# CPU_Power.net
KiCad netlist of a schematic drawn in Altium Designer
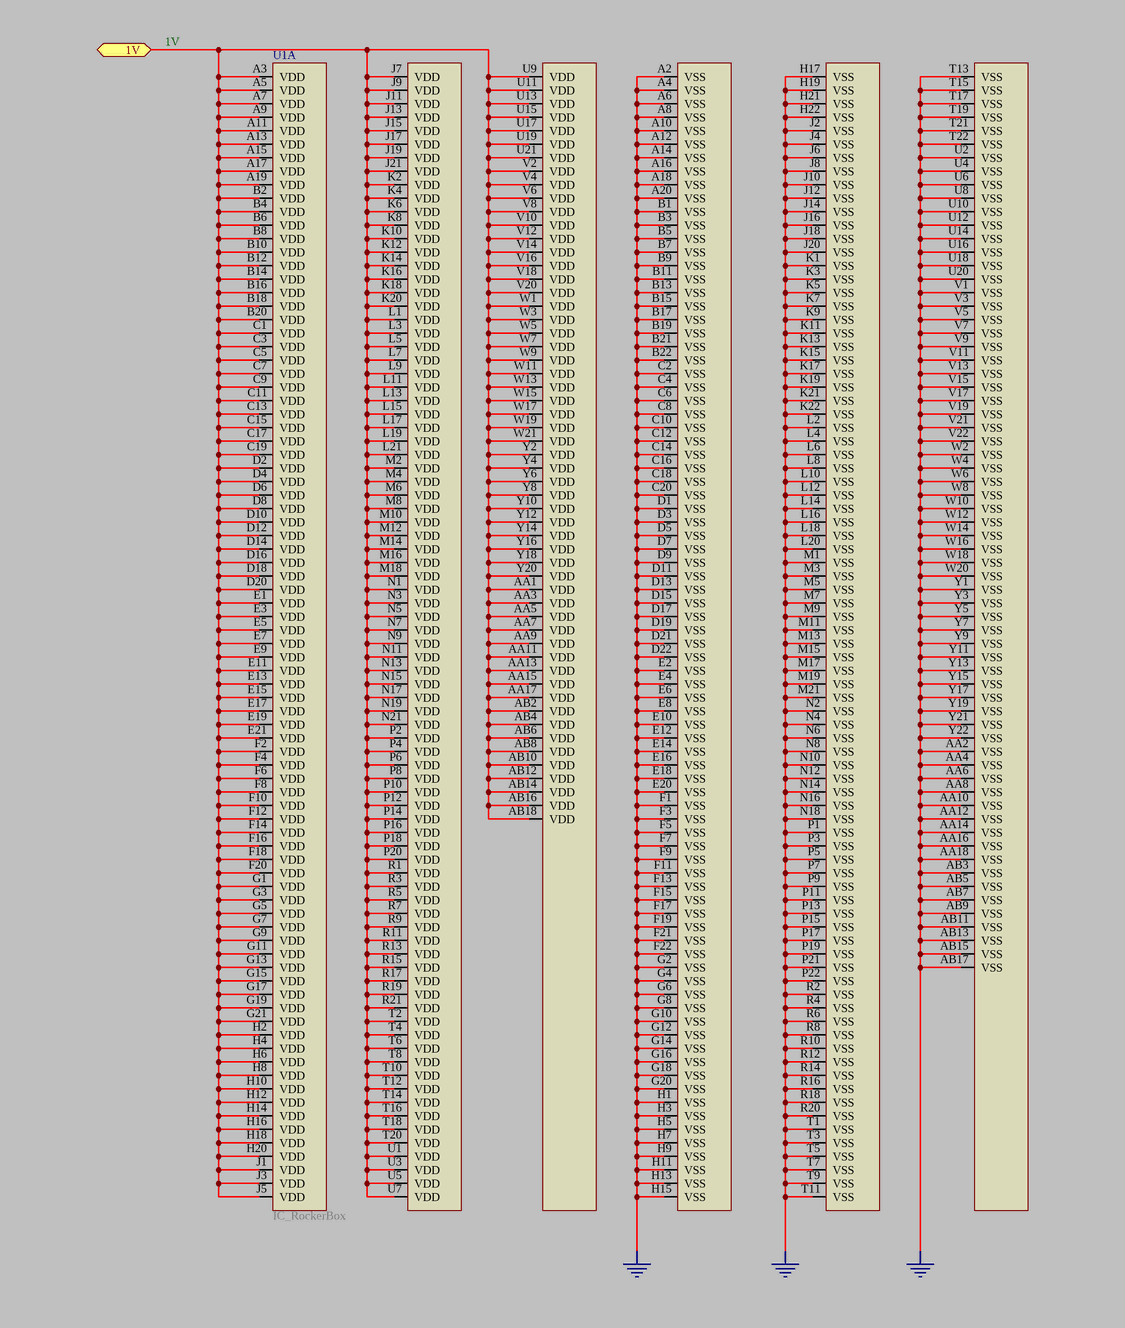
[diagram p0: CPU_Power.SchDoc, top left]
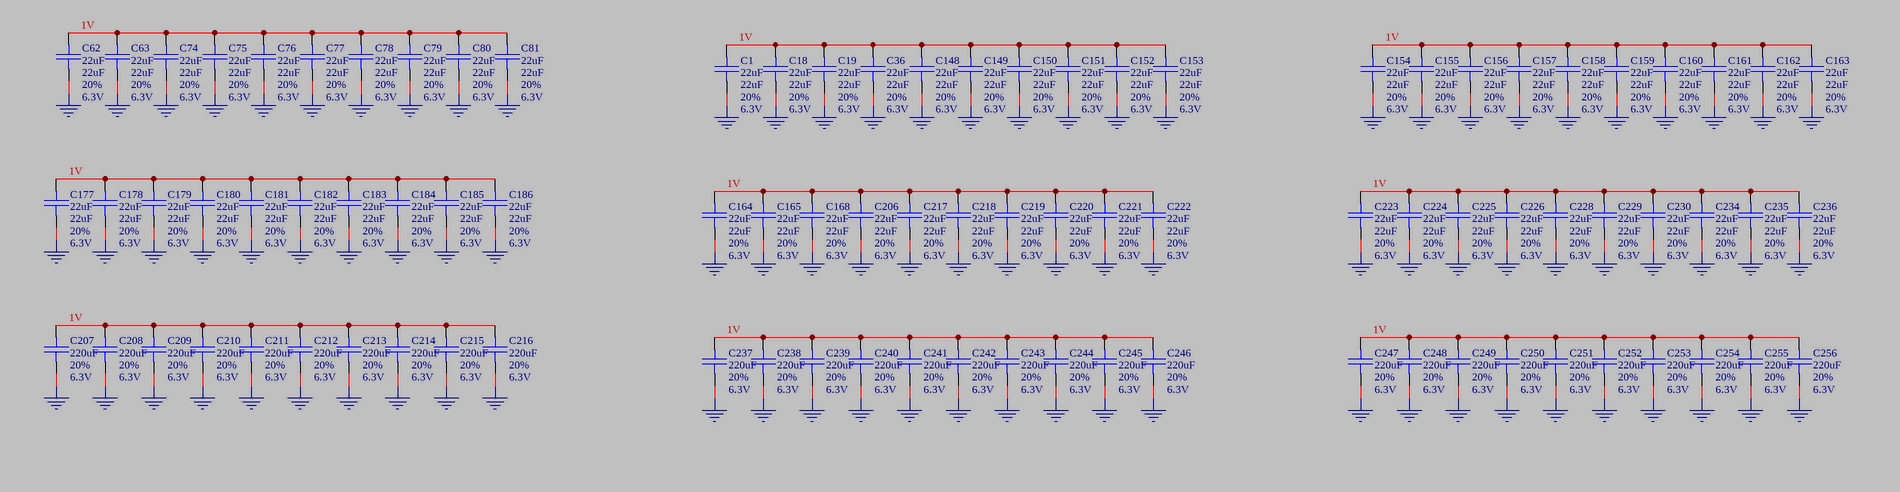
[diagram p1: CPU_Power.SchDoc, bottom left]
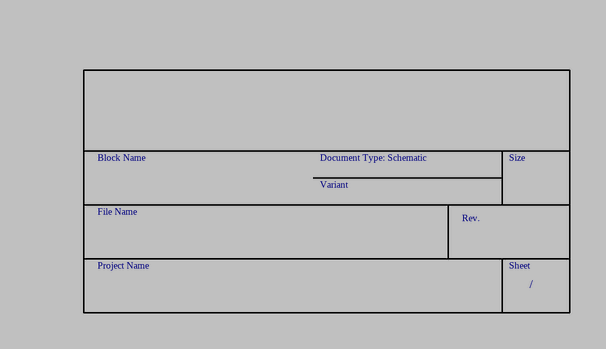
[diagram p2: CPU_Power.SchDoc, bottom right]

(export (version "E")
  (design (tool "Eeschema 10.0.6"))
  (components
    (comp (ref "C1")
      (value "22uF")
      (footprint "SMD_0805_CAPC2012X145N")
      (fields
        (field (name "DB_PART_NUMBER") "CAP000043686")
        (field (name "DB_VALUE") "22uF")
        (field (name "DB_TOLERANCE") "20%")
        (field (name "DB_VOLTAGE") "6.3V")
        (field (name "DB_MANUFACTURER_PART") "KEMET    C0805C226M9PAC")
        (field (name "DB_APPROVED_BY") "ISHIDDEN=T")
      )
      (libsource (lib "Database_Libs1") (part "C"))
    )
    (comp (ref "C18")
      (value "22uF")
      (footprint "SMD_0805_CAPC2012X145N")
      (fields
        (field (name "DB_PART_NUMBER") "CAP000043686")
        (field (name "DB_VALUE") "22uF")
        (field (name "DB_TOLERANCE") "20%")
        (field (name "DB_VOLTAGE") "6.3V")
        (field (name "DB_MANUFACTURER_PART") "KEMET    C0805C226M9PAC")
        (field (name "DB_APPROVED_BY") "ISHIDDEN=T")
      )
      (libsource (lib "Database_Libs1") (part "C"))
    )
    (comp (ref "C19")
      (value "22uF")
      (footprint "SMD_0805_CAPC2012X145N")
      (fields
        (field (name "DB_PART_NUMBER") "CAP000043686")
        (field (name "DB_VALUE") "22uF")
        (field (name "DB_TOLERANCE") "20%")
        (field (name "DB_VOLTAGE") "6.3V")
        (field (name "DB_MANUFACTURER_PART") "KEMET    C0805C226M9PAC")
        (field (name "DB_APPROVED_BY") "ISHIDDEN=T")
      )
      (libsource (lib "Database_Libs1") (part "C"))
    )
    (comp (ref "C36")
      (value "22uF")
      (footprint "SMD_0805_CAPC2012X145N")
      (fields
        (field (name "DB_PART_NUMBER") "CAP000043686")
        (field (name "DB_VALUE") "22uF")
        (field (name "DB_TOLERANCE") "20%")
        (field (name "DB_VOLTAGE") "6.3V")
        (field (name "DB_MANUFACTURER_PART") "KEMET    C0805C226M9PAC")
        (field (name "DB_APPROVED_BY") "ISHIDDEN=T")
      )
      (libsource (lib "Database_Libs1") (part "C"))
    )
    (comp (ref "C62")
      (value "22uF")
      (footprint "SMD_0805_CAPC2012X145N")
      (fields
        (field (name "DB_PART_NUMBER") "CAP000043686")
        (field (name "DB_VALUE") "22uF")
        (field (name "DB_TOLERANCE") "20%")
        (field (name "DB_VOLTAGE") "6.3V")
        (field (name "DB_MANUFACTURER_PART") "KEMET    C0805C226M9PAC")
        (field (name "DB_APPROVED_BY") "ISHIDDEN=T")
      )
      (libsource (lib "Database_Libs1") (part "C"))
    )
    (comp (ref "C63")
      (value "22uF")
      (footprint "SMD_0805_CAPC2012X145N")
      (fields
        (field (name "DB_PART_NUMBER") "CAP000043686")
        (field (name "DB_VALUE") "22uF")
        (field (name "DB_TOLERANCE") "20%")
        (field (name "DB_VOLTAGE") "6.3V")
        (field (name "DB_MANUFACTURER_PART") "KEMET    C0805C226M9PAC")
        (field (name "DB_APPROVED_BY") "ISHIDDEN=T")
      )
      (libsource (lib "Database_Libs1") (part "C"))
    )
    (comp (ref "C74")
      (value "22uF")
      (footprint "SMD_0805_CAPC2012X145N")
      (fields
        (field (name "DB_PART_NUMBER") "CAP000043686")
        (field (name "DB_VALUE") "22uF")
        (field (name "DB_TOLERANCE") "20%")
        (field (name "DB_VOLTAGE") "6.3V")
        (field (name "DB_MANUFACTURER_PART") "KEMET    C0805C226M9PAC")
        (field (name "DB_APPROVED_BY") "ISHIDDEN=T")
      )
      (libsource (lib "Database_Libs1") (part "C"))
    )
    (comp (ref "C75")
      (value "22uF")
      (footprint "SMD_0805_CAPC2012X145N")
      (fields
        (field (name "DB_PART_NUMBER") "CAP000043686")
        (field (name "DB_VALUE") "22uF")
        (field (name "DB_TOLERANCE") "20%")
        (field (name "DB_VOLTAGE") "6.3V")
        (field (name "DB_MANUFACTURER_PART") "KEMET    C0805C226M9PAC")
        (field (name "DB_APPROVED_BY") "ISHIDDEN=T")
      )
      (libsource (lib "Database_Libs1") (part "C"))
    )
    (comp (ref "C76")
      (value "22uF")
      (footprint "SMD_0805_CAPC2012X145N")
      (fields
        (field (name "DB_PART_NUMBER") "CAP000043686")
        (field (name "DB_VALUE") "22uF")
        (field (name "DB_TOLERANCE") "20%")
        (field (name "DB_VOLTAGE") "6.3V")
        (field (name "DB_MANUFACTURER_PART") "KEMET    C0805C226M9PAC")
        (field (name "DB_APPROVED_BY") "ISHIDDEN=T")
      )
      (libsource (lib "Database_Libs1") (part "C"))
    )
    (comp (ref "C77")
      (value "22uF")
      (footprint "SMD_0805_CAPC2012X145N")
      (fields
        (field (name "DB_PART_NUMBER") "CAP000043686")
        (field (name "DB_VALUE") "22uF")
        (field (name "DB_TOLERANCE") "20%")
        (field (name "DB_VOLTAGE") "6.3V")
        (field (name "DB_MANUFACTURER_PART") "KEMET    C0805C226M9PAC")
        (field (name "DB_APPROVED_BY") "ISHIDDEN=T")
      )
      (libsource (lib "Database_Libs1") (part "C"))
    )
    (comp (ref "C78")
      (value "22uF")
      (footprint "SMD_0805_CAPC2012X145N")
      (fields
        (field (name "DB_PART_NUMBER") "CAP000043686")
        (field (name "DB_VALUE") "22uF")
        (field (name "DB_TOLERANCE") "20%")
        (field (name "DB_VOLTAGE") "6.3V")
        (field (name "DB_MANUFACTURER_PART") "KEMET    C0805C226M9PAC")
        (field (name "DB_APPROVED_BY") "ISHIDDEN=T")
      )
      (libsource (lib "Database_Libs1") (part "C"))
    )
    (comp (ref "C79")
      (value "22uF")
      (footprint "SMD_0805_CAPC2012X145N")
      (fields
        (field (name "DB_PART_NUMBER") "CAP000043686")
        (field (name "DB_VALUE") "22uF")
        (field (name "DB_TOLERANCE") "20%")
        (field (name "DB_VOLTAGE") "6.3V")
        (field (name "DB_MANUFACTURER_PART") "KEMET    C0805C226M9PAC")
        (field (name "DB_APPROVED_BY") "ISHIDDEN=T")
      )
      (libsource (lib "Database_Libs1") (part "C"))
    )
    (comp (ref "C80")
      (value "22uF")
      (footprint "SMD_0805_CAPC2012X145N")
      (fields
        (field (name "DB_PART_NUMBER") "CAP000043686")
        (field (name "DB_VALUE") "22uF")
        (field (name "DB_TOLERANCE") "20%")
        (field (name "DB_VOLTAGE") "6.3V")
        (field (name "DB_MANUFACTURER_PART") "KEMET    C0805C226M9PAC")
        (field (name "DB_APPROVED_BY") "ISHIDDEN=T")
      )
      (libsource (lib "Database_Libs1") (part "C"))
    )
    (comp (ref "C81")
      (value "22uF")
      (footprint "SMD_0805_CAPC2012X145N")
      (fields
        (field (name "DB_PART_NUMBER") "CAP000043686")
        (field (name "DB_VALUE") "22uF")
        (field (name "DB_TOLERANCE") "20%")
        (field (name "DB_VOLTAGE") "6.3V")
        (field (name "DB_MANUFACTURER_PART") "KEMET    C0805C226M9PAC")
        (field (name "DB_APPROVED_BY") "ISHIDDEN=T")
      )
      (libsource (lib "Database_Libs1") (part "C"))
    )
    (comp (ref "C148")
      (value "22uF")
      (footprint "SMD_0805_CAPC2012X145N")
      (fields
        (field (name "DB_PART_NUMBER") "CAP000043686")
        (field (name "DB_VALUE") "22uF")
        (field (name "DB_TOLERANCE") "20%")
        (field (name "DB_VOLTAGE") "6.3V")
        (field (name "DB_MANUFACTURER_PART") "KEMET    C0805C226M9PAC")
        (field (name "DB_APPROVED_BY") "ISHIDDEN=T")
      )
      (libsource (lib "Database_Libs1") (part "C"))
    )
    (comp (ref "C149")
      (value "22uF")
      (footprint "SMD_0805_CAPC2012X145N")
      (fields
        (field (name "DB_PART_NUMBER") "CAP000043686")
        (field (name "DB_VALUE") "22uF")
        (field (name "DB_TOLERANCE") "20%")
        (field (name "DB_VOLTAGE") "6.3V")
        (field (name "DB_MANUFACTURER_PART") "KEMET    C0805C226M9PAC")
        (field (name "DB_APPROVED_BY") "ISHIDDEN=T")
      )
      (libsource (lib "Database_Libs1") (part "C"))
    )
    (comp (ref "C150")
      (value "22uF")
      (footprint "SMD_0805_CAPC2012X145N")
      (fields
        (field (name "DB_PART_NUMBER") "CAP000043686")
        (field (name "DB_VALUE") "22uF")
        (field (name "DB_TOLERANCE") "20%")
        (field (name "DB_VOLTAGE") "6.3V")
        (field (name "DB_MANUFACTURER_PART") "KEMET    C0805C226M9PAC")
        (field (name "DB_APPROVED_BY") "ISHIDDEN=T")
      )
      (libsource (lib "Database_Libs1") (part "C"))
    )
    (comp (ref "C151")
      (value "22uF")
      (footprint "SMD_0805_CAPC2012X145N")
      (fields
        (field (name "DB_PART_NUMBER") "CAP000043686")
        (field (name "DB_VALUE") "22uF")
        (field (name "DB_TOLERANCE") "20%")
        (field (name "DB_VOLTAGE") "6.3V")
        (field (name "DB_MANUFACTURER_PART") "KEMET    C0805C226M9PAC")
        (field (name "DB_APPROVED_BY") "ISHIDDEN=T")
      )
      (libsource (lib "Database_Libs1") (part "C"))
    )
    (comp (ref "C152")
      (value "22uF")
      (footprint "SMD_0805_CAPC2012X145N")
      (fields
        (field (name "DB_PART_NUMBER") "CAP000043686")
        (field (name "DB_VALUE") "22uF")
        (field (name "DB_TOLERANCE") "20%")
        (field (name "DB_VOLTAGE") "6.3V")
        (field (name "DB_MANUFACTURER_PART") "KEMET    C0805C226M9PAC")
        (field (name "DB_APPROVED_BY") "ISHIDDEN=T")
      )
      (libsource (lib "Database_Libs1") (part "C"))
    )
    (comp (ref "C153")
      (value "22uF")
      (footprint "SMD_0805_CAPC2012X145N")
      (fields
        (field (name "DB_PART_NUMBER") "CAP000043686")
        (field (name "DB_VALUE") "22uF")
        (field (name "DB_TOLERANCE") "20%")
        (field (name "DB_VOLTAGE") "6.3V")
        (field (name "DB_MANUFACTURER_PART") "KEMET    C0805C226M9PAC")
        (field (name "DB_APPROVED_BY") "ISHIDDEN=T")
      )
      (libsource (lib "Database_Libs1") (part "C"))
    )
    (comp (ref "C154")
      (value "22uF")
      (footprint "SMD_0805_CAPC2012X145N")
      (fields
        (field (name "DB_PART_NUMBER") "CAP000043686")
        (field (name "DB_VALUE") "22uF")
        (field (name "DB_TOLERANCE") "20%")
        (field (name "DB_VOLTAGE") "6.3V")
        (field (name "DB_MANUFACTURER_PART") "KEMET    C0805C226M9PAC")
        (field (name "DB_APPROVED_BY") "ISHIDDEN=T")
      )
      (libsource (lib "Database_Libs1") (part "C"))
    )
    (comp (ref "C155")
      (value "22uF")
      (footprint "SMD_0805_CAPC2012X145N")
      (fields
        (field (name "DB_PART_NUMBER") "CAP000043686")
        (field (name "DB_VALUE") "22uF")
        (field (name "DB_TOLERANCE") "20%")
        (field (name "DB_VOLTAGE") "6.3V")
        (field (name "DB_MANUFACTURER_PART") "KEMET    C0805C226M9PAC")
        (field (name "DB_APPROVED_BY") "ISHIDDEN=T")
      )
      (libsource (lib "Database_Libs1") (part "C"))
    )
    (comp (ref "C156")
      (value "22uF")
      (footprint "SMD_0805_CAPC2012X145N")
      (fields
        (field (name "DB_PART_NUMBER") "CAP000043686")
        (field (name "DB_VALUE") "22uF")
        (field (name "DB_TOLERANCE") "20%")
        (field (name "DB_VOLTAGE") "6.3V")
        (field (name "DB_MANUFACTURER_PART") "KEMET    C0805C226M9PAC")
        (field (name "DB_APPROVED_BY") "ISHIDDEN=T")
      )
      (libsource (lib "Database_Libs1") (part "C"))
    )
    (comp (ref "C157")
      (value "22uF")
      (footprint "SMD_0805_CAPC2012X145N")
      (fields
        (field (name "DB_PART_NUMBER") "CAP000043686")
        (field (name "DB_VALUE") "22uF")
        (field (name "DB_TOLERANCE") "20%")
        (field (name "DB_VOLTAGE") "6.3V")
        (field (name "DB_MANUFACTURER_PART") "KEMET    C0805C226M9PAC")
        (field (name "DB_APPROVED_BY") "ISHIDDEN=T")
      )
      (libsource (lib "Database_Libs1") (part "C"))
    )
    (comp (ref "C158")
      (value "22uF")
      (footprint "SMD_0805_CAPC2012X145N")
      (fields
        (field (name "DB_PART_NUMBER") "CAP000043686")
        (field (name "DB_VALUE") "22uF")
        (field (name "DB_TOLERANCE") "20%")
        (field (name "DB_VOLTAGE") "6.3V")
        (field (name "DB_MANUFACTURER_PART") "KEMET    C0805C226M9PAC")
        (field (name "DB_APPROVED_BY") "ISHIDDEN=T")
      )
      (libsource (lib "Database_Libs1") (part "C"))
    )
    (comp (ref "C159")
      (value "22uF")
      (footprint "SMD_0805_CAPC2012X145N")
      (fields
        (field (name "DB_PART_NUMBER") "CAP000043686")
        (field (name "DB_VALUE") "22uF")
        (field (name "DB_TOLERANCE") "20%")
        (field (name "DB_VOLTAGE") "6.3V")
        (field (name "DB_MANUFACTURER_PART") "KEMET    C0805C226M9PAC")
        (field (name "DB_APPROVED_BY") "ISHIDDEN=T")
      )
      (libsource (lib "Database_Libs1") (part "C"))
    )
    (comp (ref "C160")
      (value "22uF")
      (footprint "SMD_0805_CAPC2012X145N")
      (fields
        (field (name "DB_PART_NUMBER") "CAP000043686")
        (field (name "DB_VALUE") "22uF")
        (field (name "DB_TOLERANCE") "20%")
        (field (name "DB_VOLTAGE") "6.3V")
        (field (name "DB_MANUFACTURER_PART") "KEMET    C0805C226M9PAC")
        (field (name "DB_APPROVED_BY") "ISHIDDEN=T")
      )
      (libsource (lib "Database_Libs1") (part "C"))
    )
    (comp (ref "C161")
      (value "22uF")
      (footprint "SMD_0805_CAPC2012X145N")
      (fields
        (field (name "DB_PART_NUMBER") "CAP000043686")
        (field (name "DB_VALUE") "22uF")
        (field (name "DB_TOLERANCE") "20%")
        (field (name "DB_VOLTAGE") "6.3V")
        (field (name "DB_MANUFACTURER_PART") "KEMET    C0805C226M9PAC")
        (field (name "DB_APPROVED_BY") "ISHIDDEN=T")
      )
      (libsource (lib "Database_Libs1") (part "C"))
    )
    (comp (ref "C162")
      (value "22uF")
      (footprint "SMD_0805_CAPC2012X145N")
      (fields
        (field (name "DB_PART_NUMBER") "CAP000043686")
        (field (name "DB_VALUE") "22uF")
        (field (name "DB_TOLERANCE") "20%")
        (field (name "DB_VOLTAGE") "6.3V")
        (field (name "DB_MANUFACTURER_PART") "KEMET    C0805C226M9PAC")
        (field (name "DB_APPROVED_BY") "ISHIDDEN=T")
      )
      (libsource (lib "Database_Libs1") (part "C"))
    )
    (comp (ref "C163")
      (value "22uF")
      (footprint "SMD_0805_CAPC2012X145N")
      (fields
        (field (name "DB_PART_NUMBER") "CAP000043686")
        (field (name "DB_VALUE") "22uF")
        (field (name "DB_TOLERANCE") "20%")
        (field (name "DB_VOLTAGE") "6.3V")
        (field (name "DB_MANUFACTURER_PART") "KEMET    C0805C226M9PAC")
        (field (name "DB_APPROVED_BY") "ISHIDDEN=T")
      )
      (libsource (lib "Database_Libs1") (part "C"))
    )
    (comp (ref "C164")
      (value "22uF")
      (footprint "SMD_0805_CAPC2012X145N")
      (fields
        (field (name "DB_PART_NUMBER") "CAP000043686")
        (field (name "DB_VALUE") "22uF")
        (field (name "DB_TOLERANCE") "20%")
        (field (name "DB_VOLTAGE") "6.3V")
        (field (name "DB_MANUFACTURER_PART") "KEMET    C0805C226M9PAC")
        (field (name "DB_APPROVED_BY") "ISHIDDEN=T")
      )
      (libsource (lib "Database_Libs1") (part "C"))
    )
    (comp (ref "C165")
      (value "22uF")
      (footprint "SMD_0805_CAPC2012X145N")
      (fields
        (field (name "DB_PART_NUMBER") "CAP000043686")
        (field (name "DB_VALUE") "22uF")
        (field (name "DB_TOLERANCE") "20%")
        (field (name "DB_VOLTAGE") "6.3V")
        (field (name "DB_MANUFACTURER_PART") "KEMET    C0805C226M9PAC")
        (field (name "DB_APPROVED_BY") "ISHIDDEN=T")
      )
      (libsource (lib "Database_Libs1") (part "C"))
    )
    (comp (ref "C168")
      (value "22uF")
      (footprint "SMD_0805_CAPC2012X145N")
      (fields
        (field (name "DB_PART_NUMBER") "CAP000043686")
        (field (name "DB_VALUE") "22uF")
        (field (name "DB_TOLERANCE") "20%")
        (field (name "DB_VOLTAGE") "6.3V")
        (field (name "DB_MANUFACTURER_PART") "KEMET    C0805C226M9PAC")
        (field (name "DB_APPROVED_BY") "ISHIDDEN=T")
      )
      (libsource (lib "Database_Libs1") (part "C"))
    )
    (comp (ref "C177")
      (value "22uF")
      (footprint "SMD_0805_CAPC2012X145N")
      (fields
        (field (name "DB_PART_NUMBER") "CAP000043686")
        (field (name "DB_VALUE") "22uF")
        (field (name "DB_TOLERANCE") "20%")
        (field (name "DB_VOLTAGE") "6.3V")
        (field (name "DB_MANUFACTURER_PART") "KEMET    C0805C226M9PAC")
        (field (name "DB_APPROVED_BY") "ISHIDDEN=T")
      )
      (libsource (lib "Database_Libs1") (part "C"))
    )
    (comp (ref "C178")
      (value "22uF")
      (footprint "SMD_0805_CAPC2012X145N")
      (fields
        (field (name "DB_PART_NUMBER") "CAP000043686")
        (field (name "DB_VALUE") "22uF")
        (field (name "DB_TOLERANCE") "20%")
        (field (name "DB_VOLTAGE") "6.3V")
        (field (name "DB_MANUFACTURER_PART") "KEMET    C0805C226M9PAC")
        (field (name "DB_APPROVED_BY") "ISHIDDEN=T")
      )
      (libsource (lib "Database_Libs1") (part "C"))
    )
    (comp (ref "C179")
      (value "22uF")
      (footprint "SMD_0805_CAPC2012X145N")
      (fields
        (field (name "DB_PART_NUMBER") "CAP000043686")
        (field (name "DB_VALUE") "22uF")
        (field (name "DB_TOLERANCE") "20%")
        (field (name "DB_VOLTAGE") "6.3V")
        (field (name "DB_MANUFACTURER_PART") "KEMET    C0805C226M9PAC")
        (field (name "DB_APPROVED_BY") "ISHIDDEN=T")
      )
      (libsource (lib "Database_Libs1") (part "C"))
    )
    (comp (ref "C180")
      (value "22uF")
      (footprint "SMD_0805_CAPC2012X145N")
      (fields
        (field (name "DB_PART_NUMBER") "CAP000043686")
        (field (name "DB_VALUE") "22uF")
        (field (name "DB_TOLERANCE") "20%")
        (field (name "DB_VOLTAGE") "6.3V")
        (field (name "DB_MANUFACTURER_PART") "KEMET    C0805C226M9PAC")
        (field (name "DB_APPROVED_BY") "ISHIDDEN=T")
      )
      (libsource (lib "Database_Libs1") (part "C"))
    )
    (comp (ref "C181")
      (value "22uF")
      (footprint "SMD_0805_CAPC2012X145N")
      (fields
        (field (name "DB_PART_NUMBER") "CAP000043686")
        (field (name "DB_VALUE") "22uF")
        (field (name "DB_TOLERANCE") "20%")
        (field (name "DB_VOLTAGE") "6.3V")
        (field (name "DB_MANUFACTURER_PART") "KEMET    C0805C226M9PAC")
        (field (name "DB_APPROVED_BY") "ISHIDDEN=T")
      )
      (libsource (lib "Database_Libs1") (part "C"))
    )
    (comp (ref "C182")
      (value "22uF")
      (footprint "SMD_0805_CAPC2012X145N")
      (fields
        (field (name "DB_PART_NUMBER") "CAP000043686")
        (field (name "DB_VALUE") "22uF")
        (field (name "DB_TOLERANCE") "20%")
        (field (name "DB_VOLTAGE") "6.3V")
        (field (name "DB_MANUFACTURER_PART") "KEMET    C0805C226M9PAC")
        (field (name "DB_APPROVED_BY") "ISHIDDEN=T")
      )
      (libsource (lib "Database_Libs1") (part "C"))
    )
    (comp (ref "C183")
      (value "22uF")
      (footprint "SMD_0805_CAPC2012X145N")
      (fields
        (field (name "DB_PART_NUMBER") "CAP000043686")
        (field (name "DB_VALUE") "22uF")
        (field (name "DB_TOLERANCE") "20%")
        (field (name "DB_VOLTAGE") "6.3V")
        (field (name "DB_MANUFACTURER_PART") "KEMET    C0805C226M9PAC")
        (field (name "DB_APPROVED_BY") "ISHIDDEN=T")
      )
      (libsource (lib "Database_Libs1") (part "C"))
    )
    (comp (ref "C184")
      (value "22uF")
      (footprint "SMD_0805_CAPC2012X145N")
      (fields
        (field (name "DB_PART_NUMBER") "CAP000043686")
        (field (name "DB_VALUE") "22uF")
        (field (name "DB_TOLERANCE") "20%")
        (field (name "DB_VOLTAGE") "6.3V")
        (field (name "DB_MANUFACTURER_PART") "KEMET    C0805C226M9PAC")
        (field (name "DB_APPROVED_BY") "ISHIDDEN=T")
      )
      (libsource (lib "Database_Libs1") (part "C"))
    )
    (comp (ref "C185")
      (value "22uF")
      (footprint "SMD_0805_CAPC2012X145N")
      (fields
        (field (name "DB_PART_NUMBER") "CAP000043686")
        (field (name "DB_VALUE") "22uF")
        (field (name "DB_TOLERANCE") "20%")
        (field (name "DB_VOLTAGE") "6.3V")
        (field (name "DB_MANUFACTURER_PART") "KEMET    C0805C226M9PAC")
        (field (name "DB_APPROVED_BY") "ISHIDDEN=T")
      )
      (libsource (lib "Database_Libs1") (part "C"))
    )
    (comp (ref "C186")
      (value "22uF")
      (footprint "SMD_0805_CAPC2012X145N")
      (fields
        (field (name "DB_PART_NUMBER") "CAP000043686")
        (field (name "DB_VALUE") "22uF")
        (field (name "DB_TOLERANCE") "20%")
        (field (name "DB_VOLTAGE") "6.3V")
        (field (name "DB_MANUFACTURER_PART") "KEMET    C0805C226M9PAC")
        (field (name "DB_APPROVED_BY") "ISHIDDEN=T")
      )
      (libsource (lib "Database_Libs1") (part "C"))
    )
    (comp (ref "C206")
      (value "22uF")
      (footprint "SMD_0805_CAPC2012X145N")
      (fields
        (field (name "DB_PART_NUMBER") "CAP000043686")
        (field (name "DB_VALUE") "22uF")
        (field (name "DB_TOLERANCE") "20%")
        (field (name "DB_VOLTAGE") "6.3V")
        (field (name "DB_MANUFACTURER_PART") "KEMET    C0805C226M9PAC")
        (field (name "DB_APPROVED_BY") "ISHIDDEN=T")
      )
      (libsource (lib "Database_Libs1") (part "C"))
    )
    (comp (ref "C207")
      (value "220uF")
      (footprint "SMD_1210_CAPC3225X279N")
      (fields
        (field (name "DB_PART_NUMBER") "CAP000047355")
        (field (name "DB_VALUE") "220uF")
        (field (name "DB_TOLERANCE") "20%")
        (field (name "DB_VOLTAGE") "6.3V")
        (field (name "DB_MANUFACTURER_PART") "SAMSUNG    CL32A227MQVNNNE")
        (field (name "DB_APPROVED_BY") "VSN")
      )
      (libsource (lib "Database_Libs1") (part "C"))
    )
    (comp (ref "C208")
      (value "220uF")
      (footprint "SMD_1210_CAPC3225X279N")
      (fields
        (field (name "DB_PART_NUMBER") "CAP000047355")
        (field (name "DB_VALUE") "220uF")
        (field (name "DB_TOLERANCE") "20%")
        (field (name "DB_VOLTAGE") "6.3V")
        (field (name "DB_MANUFACTURER_PART") "SAMSUNG    CL32A227MQVNNNE")
        (field (name "DB_APPROVED_BY") "VSN")
      )
      (libsource (lib "Database_Libs1") (part "C"))
    )
    (comp (ref "C209")
      (value "220uF")
      (footprint "SMD_1210_CAPC3225X279N")
      (fields
        (field (name "DB_PART_NUMBER") "CAP000047355")
        (field (name "DB_VALUE") "220uF")
        (field (name "DB_TOLERANCE") "20%")
        (field (name "DB_VOLTAGE") "6.3V")
        (field (name "DB_MANUFACTURER_PART") "SAMSUNG    CL32A227MQVNNNE")
        (field (name "DB_APPROVED_BY") "VSN")
      )
      (libsource (lib "Database_Libs1") (part "C"))
    )
    (comp (ref "C210")
      (value "220uF")
      (footprint "SMD_1210_CAPC3225X279N")
      (fields
        (field (name "DB_PART_NUMBER") "CAP000047355")
        (field (name "DB_VALUE") "220uF")
        (field (name "DB_TOLERANCE") "20%")
        (field (name "DB_VOLTAGE") "6.3V")
        (field (name "DB_MANUFACTURER_PART") "SAMSUNG    CL32A227MQVNNNE")
        (field (name "DB_APPROVED_BY") "VSN")
      )
      (libsource (lib "Database_Libs1") (part "C"))
    )
    (comp (ref "C211")
      (value "220uF")
      (footprint "SMD_1210_CAPC3225X279N")
      (fields
        (field (name "DB_PART_NUMBER") "CAP000047355")
        (field (name "DB_VALUE") "220uF")
        (field (name "DB_TOLERANCE") "20%")
        (field (name "DB_VOLTAGE") "6.3V")
        (field (name "DB_MANUFACTURER_PART") "SAMSUNG    CL32A227MQVNNNE")
        (field (name "DB_APPROVED_BY") "VSN")
      )
      (libsource (lib "Database_Libs1") (part "C"))
    )
    (comp (ref "C212")
      (value "220uF")
      (footprint "SMD_1210_CAPC3225X279N")
      (fields
        (field (name "DB_PART_NUMBER") "CAP000047355")
        (field (name "DB_VALUE") "220uF")
        (field (name "DB_TOLERANCE") "20%")
        (field (name "DB_VOLTAGE") "6.3V")
        (field (name "DB_MANUFACTURER_PART") "SAMSUNG    CL32A227MQVNNNE")
        (field (name "DB_APPROVED_BY") "VSN")
      )
      (libsource (lib "Database_Libs1") (part "C"))
    )
    (comp (ref "C213")
      (value "220uF")
      (footprint "SMD_1210_CAPC3225X279N")
      (fields
        (field (name "DB_PART_NUMBER") "CAP000047355")
        (field (name "DB_VALUE") "220uF")
        (field (name "DB_TOLERANCE") "20%")
        (field (name "DB_VOLTAGE") "6.3V")
        (field (name "DB_MANUFACTURER_PART") "SAMSUNG    CL32A227MQVNNNE")
        (field (name "DB_APPROVED_BY") "VSN")
      )
      (libsource (lib "Database_Libs1") (part "C"))
    )
    (comp (ref "C214")
      (value "220uF")
      (footprint "SMD_1210_CAPC3225X279N")
      (fields
        (field (name "DB_PART_NUMBER") "CAP000047355")
        (field (name "DB_VALUE") "220uF")
        (field (name "DB_TOLERANCE") "20%")
        (field (name "DB_VOLTAGE") "6.3V")
        (field (name "DB_MANUFACTURER_PART") "SAMSUNG    CL32A227MQVNNNE")
        (field (name "DB_APPROVED_BY") "VSN")
      )
      (libsource (lib "Database_Libs1") (part "C"))
    )
    (comp (ref "C215")
      (value "220uF")
      (footprint "SMD_1210_CAPC3225X279N")
      (fields
        (field (name "DB_PART_NUMBER") "CAP000047355")
        (field (name "DB_VALUE") "220uF")
        (field (name "DB_TOLERANCE") "20%")
        (field (name "DB_VOLTAGE") "6.3V")
        (field (name "DB_MANUFACTURER_PART") "SAMSUNG    CL32A227MQVNNNE")
        (field (name "DB_APPROVED_BY") "VSN")
      )
      (libsource (lib "Database_Libs1") (part "C"))
    )
    (comp (ref "C216")
      (value "220uF")
      (footprint "SMD_1210_CAPC3225X279N")
      (fields
        (field (name "DB_PART_NUMBER") "CAP000047355")
        (field (name "DB_VALUE") "220uF")
        (field (name "DB_TOLERANCE") "20%")
        (field (name "DB_VOLTAGE") "6.3V")
        (field (name "DB_MANUFACTURER_PART") "SAMSUNG    CL32A227MQVNNNE")
        (field (name "DB_APPROVED_BY") "VSN")
      )
      (libsource (lib "Database_Libs1") (part "C"))
    )
    (comp (ref "C217")
      (value "22uF")
      (footprint "SMD_0805_CAPC2012X145N")
      (fields
        (field (name "DB_PART_NUMBER") "CAP000043686")
        (field (name "DB_VALUE") "22uF")
        (field (name "DB_TOLERANCE") "20%")
        (field (name "DB_VOLTAGE") "6.3V")
        (field (name "DB_MANUFACTURER_PART") "KEMET    C0805C226M9PAC")
        (field (name "DB_APPROVED_BY") "ISHIDDEN=T")
      )
      (libsource (lib "Database_Libs1") (part "C"))
    )
    (comp (ref "C218")
      (value "22uF")
      (footprint "SMD_0805_CAPC2012X145N")
      (fields
        (field (name "DB_PART_NUMBER") "CAP000043686")
        (field (name "DB_VALUE") "22uF")
        (field (name "DB_TOLERANCE") "20%")
        (field (name "DB_VOLTAGE") "6.3V")
        (field (name "DB_MANUFACTURER_PART") "KEMET    C0805C226M9PAC")
        (field (name "DB_APPROVED_BY") "ISHIDDEN=T")
      )
      (libsource (lib "Database_Libs1") (part "C"))
    )
    (comp (ref "C219")
      (value "22uF")
      (footprint "SMD_0805_CAPC2012X145N")
      (fields
        (field (name "DB_PART_NUMBER") "CAP000043686")
        (field (name "DB_VALUE") "22uF")
        (field (name "DB_TOLERANCE") "20%")
        (field (name "DB_VOLTAGE") "6.3V")
        (field (name "DB_MANUFACTURER_PART") "KEMET    C0805C226M9PAC")
        (field (name "DB_APPROVED_BY") "ISHIDDEN=T")
      )
      (libsource (lib "Database_Libs1") (part "C"))
    )
    (comp (ref "C220")
      (value "22uF")
      (footprint "SMD_0805_CAPC2012X145N")
      (fields
        (field (name "DB_PART_NUMBER") "CAP000043686")
        (field (name "DB_VALUE") "22uF")
        (field (name "DB_TOLERANCE") "20%")
        (field (name "DB_VOLTAGE") "6.3V")
        (field (name "DB_MANUFACTURER_PART") "KEMET    C0805C226M9PAC")
        (field (name "DB_APPROVED_BY") "ISHIDDEN=T")
      )
      (libsource (lib "Database_Libs1") (part "C"))
    )
    (comp (ref "C221")
      (value "22uF")
      (footprint "SMD_0805_CAPC2012X145N")
      (fields
        (field (name "DB_PART_NUMBER") "CAP000043686")
        (field (name "DB_VALUE") "22uF")
        (field (name "DB_TOLERANCE") "20%")
        (field (name "DB_VOLTAGE") "6.3V")
        (field (name "DB_MANUFACTURER_PART") "KEMET    C0805C226M9PAC")
        (field (name "DB_APPROVED_BY") "ISHIDDEN=T")
      )
      (libsource (lib "Database_Libs1") (part "C"))
    )
    (comp (ref "C222")
      (value "22uF")
      (footprint "SMD_0805_CAPC2012X145N")
      (fields
        (field (name "DB_PART_NUMBER") "CAP000043686")
        (field (name "DB_VALUE") "22uF")
        (field (name "DB_TOLERANCE") "20%")
        (field (name "DB_VOLTAGE") "6.3V")
        (field (name "DB_MANUFACTURER_PART") "KEMET    C0805C226M9PAC")
        (field (name "DB_APPROVED_BY") "ISHIDDEN=T")
      )
      (libsource (lib "Database_Libs1") (part "C"))
    )
    (comp (ref "C223")
      (value "22uF")
      (footprint "SMD_0805_CAPC2012X145N")
      (fields
        (field (name "DB_PART_NUMBER") "CAP000043686")
        (field (name "DB_VALUE") "22uF")
        (field (name "DB_TOLERANCE") "20%")
        (field (name "DB_VOLTAGE") "6.3V")
        (field (name "DB_MANUFACTURER_PART") "KEMET    C0805C226M9PAC")
        (field (name "DB_APPROVED_BY") "ISHIDDEN=T")
      )
      (libsource (lib "Database_Libs1") (part "C"))
    )
    (comp (ref "C224")
      (value "22uF")
      (footprint "SMD_0805_CAPC2012X145N")
      (fields
        (field (name "DB_PART_NUMBER") "CAP000043686")
        (field (name "DB_VALUE") "22uF")
        (field (name "DB_TOLERANCE") "20%")
        (field (name "DB_VOLTAGE") "6.3V")
        (field (name "DB_MANUFACTURER_PART") "KEMET    C0805C226M9PAC")
        (field (name "DB_APPROVED_BY") "ISHIDDEN=T")
      )
      (libsource (lib "Database_Libs1") (part "C"))
    )
    (comp (ref "C225")
      (value "22uF")
      (footprint "SMD_0805_CAPC2012X145N")
      (fields
        (field (name "DB_PART_NUMBER") "CAP000043686")
        (field (name "DB_VALUE") "22uF")
        (field (name "DB_TOLERANCE") "20%")
        (field (name "DB_VOLTAGE") "6.3V")
        (field (name "DB_MANUFACTURER_PART") "KEMET    C0805C226M9PAC")
        (field (name "DB_APPROVED_BY") "ISHIDDEN=T")
      )
      (libsource (lib "Database_Libs1") (part "C"))
    )
    (comp (ref "C226")
      (value "22uF")
      (footprint "SMD_0805_CAPC2012X145N")
      (fields
        (field (name "DB_PART_NUMBER") "CAP000043686")
        (field (name "DB_VALUE") "22uF")
        (field (name "DB_TOLERANCE") "20%")
        (field (name "DB_VOLTAGE") "6.3V")
        (field (name "DB_MANUFACTURER_PART") "KEMET    C0805C226M9PAC")
        (field (name "DB_APPROVED_BY") "ISHIDDEN=T")
      )
      (libsource (lib "Database_Libs1") (part "C"))
    )
    (comp (ref "C228")
      (value "22uF")
      (footprint "SMD_0805_CAPC2012X145N")
      (fields
        (field (name "DB_PART_NUMBER") "CAP000043686")
        (field (name "DB_VALUE") "22uF")
        (field (name "DB_TOLERANCE") "20%")
        (field (name "DB_VOLTAGE") "6.3V")
        (field (name "DB_MANUFACTURER_PART") "KEMET    C0805C226M9PAC")
        (field (name "DB_APPROVED_BY") "ISHIDDEN=T")
      )
      (libsource (lib "Database_Libs1") (part "C"))
    )
    (comp (ref "C229")
      (value "22uF")
      (footprint "SMD_0805_CAPC2012X145N")
      (fields
        (field (name "DB_PART_NUMBER") "CAP000043686")
        (field (name "DB_VALUE") "22uF")
        (field (name "DB_TOLERANCE") "20%")
        (field (name "DB_VOLTAGE") "6.3V")
        (field (name "DB_MANUFACTURER_PART") "KEMET    C0805C226M9PAC")
        (field (name "DB_APPROVED_BY") "ISHIDDEN=T")
      )
      (libsource (lib "Database_Libs1") (part "C"))
    )
    (comp (ref "C230")
      (value "22uF")
      (footprint "SMD_0805_CAPC2012X145N")
      (fields
        (field (name "DB_PART_NUMBER") "CAP000043686")
        (field (name "DB_VALUE") "22uF")
        (field (name "DB_TOLERANCE") "20%")
        (field (name "DB_VOLTAGE") "6.3V")
        (field (name "DB_MANUFACTURER_PART") "KEMET    C0805C226M9PAC")
        (field (name "DB_APPROVED_BY") "ISHIDDEN=T")
      )
      (libsource (lib "Database_Libs1") (part "C"))
    )
    (comp (ref "C234")
      (value "22uF")
      (footprint "SMD_0805_CAPC2012X145N")
      (fields
        (field (name "DB_PART_NUMBER") "CAP000043686")
        (field (name "DB_VALUE") "22uF")
        (field (name "DB_TOLERANCE") "20%")
        (field (name "DB_VOLTAGE") "6.3V")
        (field (name "DB_MANUFACTURER_PART") "KEMET    C0805C226M9PAC")
        (field (name "DB_APPROVED_BY") "ISHIDDEN=T")
      )
      (libsource (lib "Database_Libs1") (part "C"))
    )
    (comp (ref "C235")
      (value "22uF")
      (footprint "SMD_0805_CAPC2012X145N")
      (fields
        (field (name "DB_PART_NUMBER") "CAP000043686")
        (field (name "DB_VALUE") "22uF")
        (field (name "DB_TOLERANCE") "20%")
        (field (name "DB_VOLTAGE") "6.3V")
        (field (name "DB_MANUFACTURER_PART") "KEMET    C0805C226M9PAC")
        (field (name "DB_APPROVED_BY") "ISHIDDEN=T")
      )
      (libsource (lib "Database_Libs1") (part "C"))
    )
    (comp (ref "C236")
      (value "22uF")
      (footprint "SMD_0805_CAPC2012X145N")
      (fields
        (field (name "DB_PART_NUMBER") "CAP000043686")
        (field (name "DB_VALUE") "22uF")
        (field (name "DB_TOLERANCE") "20%")
        (field (name "DB_VOLTAGE") "6.3V")
        (field (name "DB_MANUFACTURER_PART") "KEMET    C0805C226M9PAC")
        (field (name "DB_APPROVED_BY") "ISHIDDEN=T")
      )
      (libsource (lib "Database_Libs1") (part "C"))
    )
    (comp (ref "C237")
      (value "220uF")
      (footprint "SMD_1210_CAPC3225X279N")
      (fields
        (field (name "DB_PART_NUMBER") "CAP000047355")
        (field (name "DB_VALUE") "220uF")
        (field (name "DB_TOLERANCE") "20%")
        (field (name "DB_VOLTAGE") "6.3V")
        (field (name "DB_MANUFACTURER_PART") "SAMSUNG    CL32A227MQVNNNE")
        (field (name "DB_APPROVED_BY") "VSN")
      )
      (libsource (lib "Database_Libs1") (part "C"))
    )
    (comp (ref "C238")
      (value "220uF")
      (footprint "SMD_1210_CAPC3225X279N")
      (fields
        (field (name "DB_PART_NUMBER") "CAP000047355")
        (field (name "DB_VALUE") "220uF")
        (field (name "DB_TOLERANCE") "20%")
        (field (name "DB_VOLTAGE") "6.3V")
        (field (name "DB_MANUFACTURER_PART") "SAMSUNG    CL32A227MQVNNNE")
        (field (name "DB_APPROVED_BY") "VSN")
      )
      (libsource (lib "Database_Libs1") (part "C"))
    )
    (comp (ref "C239")
      (value "220uF")
      (footprint "SMD_1210_CAPC3225X279N")
      (fields
        (field (name "DB_PART_NUMBER") "CAP000047355")
        (field (name "DB_VALUE") "220uF")
        (field (name "DB_TOLERANCE") "20%")
        (field (name "DB_VOLTAGE") "6.3V")
        (field (name "DB_MANUFACTURER_PART") "SAMSUNG    CL32A227MQVNNNE")
        (field (name "DB_APPROVED_BY") "VSN")
      )
      (libsource (lib "Database_Libs1") (part "C"))
    )
    (comp (ref "C240")
      (value "220uF")
      (footprint "SMD_1210_CAPC3225X279N")
      (fields
        (field (name "DB_PART_NUMBER") "CAP000047355")
        (field (name "DB_VALUE") "220uF")
        (field (name "DB_TOLERANCE") "20%")
        (field (name "DB_VOLTAGE") "6.3V")
        (field (name "DB_MANUFACTURER_PART") "SAMSUNG    CL32A227MQVNNNE")
        (field (name "DB_APPROVED_BY") "VSN")
      )
      (libsource (lib "Database_Libs1") (part "C"))
    )
    (comp (ref "C241")
      (value "220uF")
      (footprint "SMD_1210_CAPC3225X279N")
      (fields
        (field (name "DB_PART_NUMBER") "CAP000047355")
        (field (name "DB_VALUE") "220uF")
        (field (name "DB_TOLERANCE") "20%")
        (field (name "DB_VOLTAGE") "6.3V")
        (field (name "DB_MANUFACTURER_PART") "SAMSUNG    CL32A227MQVNNNE")
        (field (name "DB_APPROVED_BY") "VSN")
      )
      (libsource (lib "Database_Libs1") (part "C"))
    )
    (comp (ref "C242")
      (value "220uF")
      (footprint "SMD_1210_CAPC3225X279N")
      (fields
        (field (name "DB_PART_NUMBER") "CAP000047355")
        (field (name "DB_VALUE") "220uF")
        (field (name "DB_TOLERANCE") "20%")
        (field (name "DB_VOLTAGE") "6.3V")
        (field (name "DB_MANUFACTURER_PART") "SAMSUNG    CL32A227MQVNNNE")
        (field (name "DB_APPROVED_BY") "VSN")
      )
      (libsource (lib "Database_Libs1") (part "C"))
    )
    (comp (ref "C243")
      (value "220uF")
      (footprint "SMD_1210_CAPC3225X279N")
      (fields
        (field (name "DB_PART_NUMBER") "CAP000047355")
        (field (name "DB_VALUE") "220uF")
        (field (name "DB_TOLERANCE") "20%")
        (field (name "DB_VOLTAGE") "6.3V")
        (field (name "DB_MANUFACTURER_PART") "SAMSUNG    CL32A227MQVNNNE")
        (field (name "DB_APPROVED_BY") "VSN")
      )
      (libsource (lib "Database_Libs1") (part "C"))
    )
    (comp (ref "C244")
      (value "220uF")
      (footprint "SMD_1210_CAPC3225X279N")
      (fields
        (field (name "DB_PART_NUMBER") "CAP000047355")
        (field (name "DB_VALUE") "220uF")
        (field (name "DB_TOLERANCE") "20%")
        (field (name "DB_VOLTAGE") "6.3V")
        (field (name "DB_MANUFACTURER_PART") "SAMSUNG    CL32A227MQVNNNE")
        (field (name "DB_APPROVED_BY") "VSN")
      )
      (libsource (lib "Database_Libs1") (part "C"))
    )
    (comp (ref "C245")
      (value "220uF")
      (footprint "SMD_1210_CAPC3225X279N")
      (fields
        (field (name "DB_PART_NUMBER") "CAP000047355")
        (field (name "DB_VALUE") "220uF")
        (field (name "DB_TOLERANCE") "20%")
        (field (name "DB_VOLTAGE") "6.3V")
        (field (name "DB_MANUFACTURER_PART") "SAMSUNG    CL32A227MQVNNNE")
        (field (name "DB_APPROVED_BY") "VSN")
      )
      (libsource (lib "Database_Libs1") (part "C"))
    )
    (comp (ref "C246")
      (value "220uF")
      (footprint "SMD_1210_CAPC3225X279N")
      (fields
        (field (name "DB_PART_NUMBER") "CAP000047355")
        (field (name "DB_VALUE") "220uF")
        (field (name "DB_TOLERANCE") "20%")
        (field (name "DB_VOLTAGE") "6.3V")
        (field (name "DB_MANUFACTURER_PART") "SAMSUNG    CL32A227MQVNNNE")
        (field (name "DB_APPROVED_BY") "VSN")
      )
      (libsource (lib "Database_Libs1") (part "C"))
    )
    (comp (ref "C247")
      (value "220uF")
      (footprint "SMD_1210_CAPC3225X279N")
      (fields
        (field (name "DB_PART_NUMBER") "CAP000047355")
        (field (name "DB_VALUE") "220uF")
        (field (name "DB_TOLERANCE") "20%")
        (field (name "DB_VOLTAGE") "6.3V")
        (field (name "DB_MANUFACTURER_PART") "SAMSUNG    CL32A227MQVNNNE")
        (field (name "DB_APPROVED_BY") "VSN")
      )
      (libsource (lib "Database_Libs1") (part "C"))
    )
    (comp (ref "C248")
      (value "220uF")
      (footprint "SMD_1210_CAPC3225X279N")
      (fields
        (field (name "DB_PART_NUMBER") "CAP000047355")
        (field (name "DB_VALUE") "220uF")
        (field (name "DB_TOLERANCE") "20%")
        (field (name "DB_VOLTAGE") "6.3V")
        (field (name "DB_MANUFACTURER_PART") "SAMSUNG    CL32A227MQVNNNE")
        (field (name "DB_APPROVED_BY") "VSN")
      )
      (libsource (lib "Database_Libs1") (part "C"))
    )
    (comp (ref "C249")
      (value "220uF")
      (footprint "SMD_1210_CAPC3225X279N")
      (fields
        (field (name "DB_PART_NUMBER") "CAP000047355")
        (field (name "DB_VALUE") "220uF")
        (field (name "DB_TOLERANCE") "20%")
        (field (name "DB_VOLTAGE") "6.3V")
        (field (name "DB_MANUFACTURER_PART") "SAMSUNG    CL32A227MQVNNNE")
        (field (name "DB_APPROVED_BY") "VSN")
      )
      (libsource (lib "Database_Libs1") (part "C"))
    )
    (comp (ref "C250")
      (value "220uF")
      (footprint "SMD_1210_CAPC3225X279N")
      (fields
        (field (name "DB_PART_NUMBER") "CAP000047355")
        (field (name "DB_VALUE") "220uF")
        (field (name "DB_TOLERANCE") "20%")
        (field (name "DB_VOLTAGE") "6.3V")
        (field (name "DB_MANUFACTURER_PART") "SAMSUNG    CL32A227MQVNNNE")
        (field (name "DB_APPROVED_BY") "VSN")
      )
      (libsource (lib "Database_Libs1") (part "C"))
    )
    (comp (ref "C251")
      (value "220uF")
      (footprint "SMD_1210_CAPC3225X279N")
      (fields
        (field (name "DB_PART_NUMBER") "CAP000047355")
        (field (name "DB_VALUE") "220uF")
        (field (name "DB_TOLERANCE") "20%")
        (field (name "DB_VOLTAGE") "6.3V")
        (field (name "DB_MANUFACTURER_PART") "SAMSUNG    CL32A227MQVNNNE")
        (field (name "DB_APPROVED_BY") "VSN")
      )
      (libsource (lib "Database_Libs1") (part "C"))
    )
    (comp (ref "C252")
      (value "220uF")
      (footprint "SMD_1210_CAPC3225X279N")
      (fields
        (field (name "DB_PART_NUMBER") "CAP000047355")
        (field (name "DB_VALUE") "220uF")
        (field (name "DB_TOLERANCE") "20%")
        (field (name "DB_VOLTAGE") "6.3V")
        (field (name "DB_MANUFACTURER_PART") "SAMSUNG    CL32A227MQVNNNE")
        (field (name "DB_APPROVED_BY") "VSN")
      )
      (libsource (lib "Database_Libs1") (part "C"))
    )
    (comp (ref "C253")
      (value "220uF")
      (footprint "SMD_1210_CAPC3225X279N")
      (fields
        (field (name "DB_PART_NUMBER") "CAP000047355")
        (field (name "DB_VALUE") "220uF")
        (field (name "DB_TOLERANCE") "20%")
        (field (name "DB_VOLTAGE") "6.3V")
        (field (name "DB_MANUFACTURER_PART") "SAMSUNG    CL32A227MQVNNNE")
        (field (name "DB_APPROVED_BY") "VSN")
      )
      (libsource (lib "Database_Libs1") (part "C"))
    )
    (comp (ref "C254")
      (value "220uF")
      (footprint "SMD_1210_CAPC3225X279N")
      (fields
        (field (name "DB_PART_NUMBER") "CAP000047355")
        (field (name "DB_VALUE") "220uF")
        (field (name "DB_TOLERANCE") "20%")
        (field (name "DB_VOLTAGE") "6.3V")
        (field (name "DB_MANUFACTURER_PART") "SAMSUNG    CL32A227MQVNNNE")
        (field (name "DB_APPROVED_BY") "VSN")
      )
      (libsource (lib "Database_Libs1") (part "C"))
    )
    (comp (ref "C255")
      (value "220uF")
      (footprint "SMD_1210_CAPC3225X279N")
      (fields
        (field (name "DB_PART_NUMBER") "CAP000047355")
        (field (name "DB_VALUE") "220uF")
        (field (name "DB_TOLERANCE") "20%")
        (field (name "DB_VOLTAGE") "6.3V")
        (field (name "DB_MANUFACTURER_PART") "SAMSUNG    CL32A227MQVNNNE")
        (field (name "DB_APPROVED_BY") "VSN")
      )
      (libsource (lib "Database_Libs1") (part "C"))
    )
    (comp (ref "C256")
      (value "220uF")
      (footprint "SMD_1210_CAPC3225X279N")
      (fields
        (field (name "DB_PART_NUMBER") "CAP000047355")
        (field (name "DB_VALUE") "220uF")
        (field (name "DB_TOLERANCE") "20%")
        (field (name "DB_VOLTAGE") "6.3V")
        (field (name "DB_MANUFACTURER_PART") "SAMSUNG    CL32A227MQVNNNE")
        (field (name "DB_APPROVED_BY") "VSN")
      )
      (libsource (lib "Database_Libs1") (part "C"))
    )
    (comp (ref "U1")
      (value "IC_RockerBox")
      (footprint "SMD_BGA480C80P22X22")
      (libsource (lib "RockerBox") (part "IC_RockerBox"))
    )
  )
  (nets
    (net (code "1") (name "/1V") (class "Default")
      (node (ref "C1") (pin "2") (pinfunction "2_2") (pintype "passive"))
      (node (ref "C148") (pin "2") (pinfunction "2_2") (pintype "passive"))
      (node (ref "C149") (pin "2") (pinfunction "2_2") (pintype "passive"))
      (node (ref "C150") (pin "2") (pinfunction "2_2") (pintype "passive"))
      (node (ref "C151") (pin "2") (pinfunction "2_2") (pintype "passive"))
      (node (ref "C152") (pin "2") (pinfunction "2_2") (pintype "passive"))
      (node (ref "C153") (pin "2") (pinfunction "2_2") (pintype "passive"))
      (node (ref "C154") (pin "2") (pinfunction "2_2") (pintype "passive"))
      (node (ref "C155") (pin "2") (pinfunction "2_2") (pintype "passive"))
      (node (ref "C156") (pin "2") (pinfunction "2_2") (pintype "passive"))
      (node (ref "C157") (pin "2") (pinfunction "2_2") (pintype "passive"))
      (node (ref "C158") (pin "2") (pinfunction "2_2") (pintype "passive"))
      (node (ref "C159") (pin "2") (pinfunction "2_2") (pintype "passive"))
      (node (ref "C160") (pin "2") (pinfunction "2_2") (pintype "passive"))
      (node (ref "C161") (pin "2") (pinfunction "2_2") (pintype "passive"))
      (node (ref "C162") (pin "2") (pinfunction "2_2") (pintype "passive"))
      (node (ref "C163") (pin "2") (pinfunction "2_2") (pintype "passive"))
      (node (ref "C164") (pin "2") (pinfunction "2_2") (pintype "passive"))
      (node (ref "C165") (pin "2") (pinfunction "2_2") (pintype "passive"))
      (node (ref "C168") (pin "2") (pinfunction "2_2") (pintype "passive"))
      (node (ref "C177") (pin "2") (pinfunction "2_2") (pintype "passive"))
      (node (ref "C178") (pin "2") (pinfunction "2_2") (pintype "passive"))
      (node (ref "C179") (pin "2") (pinfunction "2_2") (pintype "passive"))
      (node (ref "C18") (pin "2") (pinfunction "2_2") (pintype "passive"))
      (node (ref "C180") (pin "2") (pinfunction "2_2") (pintype "passive"))
      (node (ref "C181") (pin "2") (pinfunction "2_2") (pintype "passive"))
      (node (ref "C182") (pin "2") (pinfunction "2_2") (pintype "passive"))
      (node (ref "C183") (pin "2") (pinfunction "2_2") (pintype "passive"))
      (node (ref "C184") (pin "2") (pinfunction "2_2") (pintype "passive"))
      (node (ref "C185") (pin "2") (pinfunction "2_2") (pintype "passive"))
      (node (ref "C186") (pin "2") (pinfunction "2_2") (pintype "passive"))
      (node (ref "C19") (pin "2") (pinfunction "2_2") (pintype "passive"))
      (node (ref "C206") (pin "2") (pinfunction "2_2") (pintype "passive"))
      (node (ref "C207") (pin "2") (pinfunction "2_2") (pintype "passive"))
      (node (ref "C208") (pin "2") (pinfunction "2_2") (pintype "passive"))
      (node (ref "C209") (pin "2") (pinfunction "2_2") (pintype "passive"))
      (node (ref "C210") (pin "2") (pinfunction "2_2") (pintype "passive"))
      (node (ref "C211") (pin "2") (pinfunction "2_2") (pintype "passive"))
      (node (ref "C212") (pin "2") (pinfunction "2_2") (pintype "passive"))
      (node (ref "C213") (pin "2") (pinfunction "2_2") (pintype "passive"))
      (node (ref "C214") (pin "2") (pinfunction "2_2") (pintype "passive"))
      (node (ref "C215") (pin "2") (pinfunction "2_2") (pintype "passive"))
      (node (ref "C216") (pin "2") (pinfunction "2_2") (pintype "passive"))
      (node (ref "C217") (pin "2") (pinfunction "2_2") (pintype "passive"))
      (node (ref "C218") (pin "2") (pinfunction "2_2") (pintype "passive"))
      (node (ref "C219") (pin "2") (pinfunction "2_2") (pintype "passive"))
      (node (ref "C220") (pin "2") (pinfunction "2_2") (pintype "passive"))
      (node (ref "C221") (pin "2") (pinfunction "2_2") (pintype "passive"))
      (node (ref "C222") (pin "2") (pinfunction "2_2") (pintype "passive"))
      (node (ref "C223") (pin "2") (pinfunction "2_2") (pintype "passive"))
      (node (ref "C224") (pin "2") (pinfunction "2_2") (pintype "passive"))
      (node (ref "C225") (pin "2") (pinfunction "2_2") (pintype "passive"))
      (node (ref "C226") (pin "2") (pinfunction "2_2") (pintype "passive"))
      (node (ref "C228") (pin "2") (pinfunction "2_2") (pintype "passive"))
      (node (ref "C229") (pin "2") (pinfunction "2_2") (pintype "passive"))
      (node (ref "C230") (pin "2") (pinfunction "2_2") (pintype "passive"))
      (node (ref "C234") (pin "2") (pinfunction "2_2") (pintype "passive"))
      (node (ref "C235") (pin "2") (pinfunction "2_2") (pintype "passive"))
      (node (ref "C236") (pin "2") (pinfunction "2_2") (pintype "passive"))
      (node (ref "C237") (pin "2") (pinfunction "2_2") (pintype "passive"))
      (node (ref "C238") (pin "2") (pinfunction "2_2") (pintype "passive"))
      (node (ref "C239") (pin "2") (pinfunction "2_2") (pintype "passive"))
      (node (ref "C240") (pin "2") (pinfunction "2_2") (pintype "passive"))
      (node (ref "C241") (pin "2") (pinfunction "2_2") (pintype "passive"))
      (node (ref "C242") (pin "2") (pinfunction "2_2") (pintype "passive"))
      (node (ref "C243") (pin "2") (pinfunction "2_2") (pintype "passive"))
      (node (ref "C244") (pin "2") (pinfunction "2_2") (pintype "passive"))
      (node (ref "C245") (pin "2") (pinfunction "2_2") (pintype "passive"))
      (node (ref "C246") (pin "2") (pinfunction "2_2") (pintype "passive"))
      (node (ref "C247") (pin "2") (pinfunction "2_2") (pintype "passive"))
      (node (ref "C248") (pin "2") (pinfunction "2_2") (pintype "passive"))
      (node (ref "C249") (pin "2") (pinfunction "2_2") (pintype "passive"))
      (node (ref "C250") (pin "2") (pinfunction "2_2") (pintype "passive"))
      (node (ref "C251") (pin "2") (pinfunction "2_2") (pintype "passive"))
      (node (ref "C252") (pin "2") (pinfunction "2_2") (pintype "passive"))
      (node (ref "C253") (pin "2") (pinfunction "2_2") (pintype "passive"))
      (node (ref "C254") (pin "2") (pinfunction "2_2") (pintype "passive"))
      (node (ref "C255") (pin "2") (pinfunction "2_2") (pintype "passive"))
      (node (ref "C256") (pin "2") (pinfunction "2_2") (pintype "passive"))
      (node (ref "C36") (pin "2") (pinfunction "2_2") (pintype "passive"))
      (node (ref "C62") (pin "2") (pinfunction "2_2") (pintype "passive"))
      (node (ref "C63") (pin "2") (pinfunction "2_2") (pintype "passive"))
      (node (ref "C74") (pin "2") (pinfunction "2_2") (pintype "passive"))
      (node (ref "C75") (pin "2") (pinfunction "2_2") (pintype "passive"))
      (node (ref "C76") (pin "2") (pinfunction "2_2") (pintype "passive"))
      (node (ref "C77") (pin "2") (pinfunction "2_2") (pintype "passive"))
      (node (ref "C78") (pin "2") (pinfunction "2_2") (pintype "passive"))
      (node (ref "C79") (pin "2") (pinfunction "2_2") (pintype "passive"))
      (node (ref "C80") (pin "2") (pinfunction "2_2") (pintype "passive"))
      (node (ref "C81") (pin "2") (pinfunction "2_2") (pintype "passive"))
      (node (ref "U1") (pin "A11") (pinfunction "VDD_A11") (pintype "passive"))
      (node (ref "U1") (pin "A13") (pinfunction "VDD_A13") (pintype "passive"))
      (node (ref "U1") (pin "A15") (pinfunction "VDD_A15") (pintype "passive"))
      (node (ref "U1") (pin "A17") (pinfunction "VDD_A17") (pintype "passive"))
      (node (ref "U1") (pin "A19") (pinfunction "VDD_A19") (pintype "passive"))
      (node (ref "U1") (pin "A3") (pinfunction "VDD_A3") (pintype "passive"))
      (node (ref "U1") (pin "A5") (pinfunction "VDD_A5") (pintype "passive"))
      (node (ref "U1") (pin "A7") (pinfunction "VDD_A7") (pintype "passive"))
      (node (ref "U1") (pin "A9") (pinfunction "VDD_A9") (pintype "passive"))
      (node (ref "U1") (pin "AA1") (pinfunction "VDD_AA1") (pintype "passive"))
      (node (ref "U1") (pin "AA11") (pinfunction "VDD_AA11") (pintype "passive"))
      (node (ref "U1") (pin "AA13") (pinfunction "VDD_AA13") (pintype "passive"))
      (node (ref "U1") (pin "AA15") (pinfunction "VDD_AA15") (pintype "passive"))
      (node (ref "U1") (pin "AA17") (pinfunction "VDD_AA17") (pintype "passive"))
      (node (ref "U1") (pin "AA3") (pinfunction "VDD_AA3") (pintype "passive"))
      (node (ref "U1") (pin "AA5") (pinfunction "VDD_AA5") (pintype "passive"))
      (node (ref "U1") (pin "AA7") (pinfunction "VDD_AA7") (pintype "passive"))
      (node (ref "U1") (pin "AA9") (pinfunction "VDD_AA9") (pintype "passive"))
      (node (ref "U1") (pin "AB10") (pinfunction "VDD_AB10") (pintype "passive"))
      (node (ref "U1") (pin "AB12") (pinfunction "VDD_AB12") (pintype "passive"))
      (node (ref "U1") (pin "AB14") (pinfunction "VDD_AB14") (pintype "passive"))
      (node (ref "U1") (pin "AB16") (pinfunction "VDD_AB16") (pintype "passive"))
      (node (ref "U1") (pin "AB18") (pinfunction "VDD_AB18") (pintype "passive"))
      (node (ref "U1") (pin "AB2") (pinfunction "VDD_AB2") (pintype "passive"))
      (node (ref "U1") (pin "AB4") (pinfunction "VDD_AB4") (pintype "passive"))
      (node (ref "U1") (pin "AB6") (pinfunction "VDD_AB6") (pintype "passive"))
      (node (ref "U1") (pin "AB8") (pinfunction "VDD_AB8") (pintype "passive"))
      (node (ref "U1") (pin "B10") (pinfunction "VDD_B10") (pintype "passive"))
      (node (ref "U1") (pin "B12") (pinfunction "VDD_B12") (pintype "passive"))
      (node (ref "U1") (pin "B14") (pinfunction "VDD_B14") (pintype "passive"))
      (node (ref "U1") (pin "B16") (pinfunction "VDD_B16") (pintype "passive"))
      (node (ref "U1") (pin "B18") (pinfunction "VDD_B18") (pintype "passive"))
      (node (ref "U1") (pin "B2") (pinfunction "VDD_B2") (pintype "passive"))
      (node (ref "U1") (pin "B20") (pinfunction "VDD_B20") (pintype "passive"))
      (node (ref "U1") (pin "B4") (pinfunction "VDD_B4") (pintype "passive"))
      (node (ref "U1") (pin "B6") (pinfunction "VDD_B6") (pintype "passive"))
      (node (ref "U1") (pin "B8") (pinfunction "VDD_B8") (pintype "passive"))
      (node (ref "U1") (pin "C1") (pinfunction "VDD_C1") (pintype "passive"))
      (node (ref "U1") (pin "C11") (pinfunction "VDD_C11") (pintype "passive"))
      (node (ref "U1") (pin "C13") (pinfunction "VDD_C13") (pintype "passive"))
      (node (ref "U1") (pin "C15") (pinfunction "VDD_C15") (pintype "passive"))
      (node (ref "U1") (pin "C17") (pinfunction "VDD_C17") (pintype "passive"))
      (node (ref "U1") (pin "C19") (pinfunction "VDD_C19") (pintype "passive"))
      (node (ref "U1") (pin "C3") (pinfunction "VDD_C3") (pintype "passive"))
      (node (ref "U1") (pin "C5") (pinfunction "VDD_C5") (pintype "passive"))
      (node (ref "U1") (pin "C7") (pinfunction "VDD_C7") (pintype "passive"))
      (node (ref "U1") (pin "C9") (pinfunction "VDD_C9") (pintype "passive"))
      (node (ref "U1") (pin "D10") (pinfunction "VDD_D10") (pintype "passive"))
      (node (ref "U1") (pin "D12") (pinfunction "VDD_D12") (pintype "passive"))
      (node (ref "U1") (pin "D14") (pinfunction "VDD_D14") (pintype "passive"))
      (node (ref "U1") (pin "D16") (pinfunction "VDD_D16") (pintype "passive"))
      (node (ref "U1") (pin "D18") (pinfunction "VDD_D18") (pintype "passive"))
      (node (ref "U1") (pin "D2") (pinfunction "VDD_D2") (pintype "passive"))
      (node (ref "U1") (pin "D20") (pinfunction "VDD_D20") (pintype "passive"))
      (node (ref "U1") (pin "D4") (pinfunction "VDD_D4") (pintype "passive"))
      (node (ref "U1") (pin "D6") (pinfunction "VDD_D6") (pintype "passive"))
      (node (ref "U1") (pin "D8") (pinfunction "VDD_D8") (pintype "passive"))
      (node (ref "U1") (pin "E1") (pinfunction "VDD_E1") (pintype "passive"))
      (node (ref "U1") (pin "E11") (pinfunction "VDD_E11") (pintype "passive"))
      (node (ref "U1") (pin "E13") (pinfunction "VDD_E13") (pintype "passive"))
      (node (ref "U1") (pin "E15") (pinfunction "VDD_E15") (pintype "passive"))
      (node (ref "U1") (pin "E17") (pinfunction "VDD_E17") (pintype "passive"))
      (node (ref "U1") (pin "E19") (pinfunction "VDD_E19") (pintype "passive"))
      (node (ref "U1") (pin "E21") (pinfunction "VDD_E21") (pintype "passive"))
      (node (ref "U1") (pin "E3") (pinfunction "VDD_E3") (pintype "passive"))
      (node (ref "U1") (pin "E5") (pinfunction "VDD_E5") (pintype "passive"))
      (node (ref "U1") (pin "E7") (pinfunction "VDD_E7") (pintype "passive"))
      (node (ref "U1") (pin "E9") (pinfunction "VDD_E9") (pintype "passive"))
      (node (ref "U1") (pin "F10") (pinfunction "VDD_F10") (pintype "passive"))
      (node (ref "U1") (pin "F12") (pinfunction "VDD_F12") (pintype "passive"))
      (node (ref "U1") (pin "F14") (pinfunction "VDD_F14") (pintype "passive"))
      (node (ref "U1") (pin "F16") (pinfunction "VDD_F16") (pintype "passive"))
      (node (ref "U1") (pin "F18") (pinfunction "VDD_F18") (pintype "passive"))
      (node (ref "U1") (pin "F2") (pinfunction "VDD_F2") (pintype "passive"))
      (node (ref "U1") (pin "F20") (pinfunction "VDD_F20") (pintype "passive"))
      (node (ref "U1") (pin "F4") (pinfunction "VDD_F4") (pintype "passive"))
      (node (ref "U1") (pin "F6") (pinfunction "VDD_F6") (pintype "passive"))
      (node (ref "U1") (pin "F8") (pinfunction "VDD_F8") (pintype "passive"))
      (node (ref "U1") (pin "G1") (pinfunction "VDD_G1") (pintype "passive"))
      (node (ref "U1") (pin "G11") (pinfunction "VDD_G11") (pintype "passive"))
      (node (ref "U1") (pin "G13") (pinfunction "VDD_G13") (pintype "passive"))
      (node (ref "U1") (pin "G15") (pinfunction "VDD_G15") (pintype "passive"))
      (node (ref "U1") (pin "G17") (pinfunction "VDD_G17") (pintype "passive"))
      (node (ref "U1") (pin "G19") (pinfunction "VDD_G19") (pintype "passive"))
      (node (ref "U1") (pin "G21") (pinfunction "VDD_G21") (pintype "passive"))
      (node (ref "U1") (pin "G3") (pinfunction "VDD_G3") (pintype "passive"))
      (node (ref "U1") (pin "G5") (pinfunction "VDD_G5") (pintype "passive"))
      (node (ref "U1") (pin "G7") (pinfunction "VDD_G7") (pintype "passive"))
      (node (ref "U1") (pin "G9") (pinfunction "VDD_G9") (pintype "passive"))
      (node (ref "U1") (pin "H10") (pinfunction "VDD_H10") (pintype "passive"))
      (node (ref "U1") (pin "H12") (pinfunction "VDD_H12") (pintype "passive"))
      (node (ref "U1") (pin "H14") (pinfunction "VDD_H14") (pintype "passive"))
      (node (ref "U1") (pin "H16") (pinfunction "VDD_H16") (pintype "passive"))
      (node (ref "U1") (pin "H18") (pinfunction "VDD_H18") (pintype "passive"))
      (node (ref "U1") (pin "H2") (pinfunction "VDD_H2") (pintype "passive"))
      (node (ref "U1") (pin "H20") (pinfunction "VDD_H20") (pintype "passive"))
      (node (ref "U1") (pin "H4") (pinfunction "VDD_H4") (pintype "passive"))
      (node (ref "U1") (pin "H6") (pinfunction "VDD_H6") (pintype "passive"))
      (node (ref "U1") (pin "H8") (pinfunction "VDD_H8") (pintype "passive"))
      (node (ref "U1") (pin "J1") (pinfunction "VDD_J1") (pintype "passive"))
      (node (ref "U1") (pin "J11") (pinfunction "VDD_J11") (pintype "passive"))
      (node (ref "U1") (pin "J13") (pinfunction "VDD_J13") (pintype "passive"))
      (node (ref "U1") (pin "J15") (pinfunction "VDD_J15") (pintype "passive"))
      (node (ref "U1") (pin "J17") (pinfunction "VDD_J17") (pintype "passive"))
      (node (ref "U1") (pin "J19") (pinfunction "VDD_J19") (pintype "passive"))
      (node (ref "U1") (pin "J21") (pinfunction "VDD_J21") (pintype "passive"))
      (node (ref "U1") (pin "J3") (pinfunction "VDD_J3") (pintype "passive"))
      (node (ref "U1") (pin "J5") (pinfunction "VDD_J5") (pintype "passive"))
      (node (ref "U1") (pin "J7") (pinfunction "VDD_J7") (pintype "passive"))
      (node (ref "U1") (pin "J9") (pinfunction "VDD_J9") (pintype "passive"))
      (node (ref "U1") (pin "K10") (pinfunction "VDD_K10") (pintype "passive"))
      (node (ref "U1") (pin "K12") (pinfunction "VDD_K12") (pintype "passive"))
      (node (ref "U1") (pin "K14") (pinfunction "VDD_K14") (pintype "passive"))
      (node (ref "U1") (pin "K16") (pinfunction "VDD_K16") (pintype "passive"))
      (node (ref "U1") (pin "K18") (pinfunction "VDD_K18") (pintype "passive"))
      (node (ref "U1") (pin "K2") (pinfunction "VDD_K2") (pintype "passive"))
      (node (ref "U1") (pin "K20") (pinfunction "VDD_K20") (pintype "passive"))
      (node (ref "U1") (pin "K4") (pinfunction "VDD_K4") (pintype "passive"))
      (node (ref "U1") (pin "K6") (pinfunction "VDD_K6") (pintype "passive"))
      (node (ref "U1") (pin "K8") (pinfunction "VDD_K8") (pintype "passive"))
      (node (ref "U1") (pin "L1") (pinfunction "VDD_L1") (pintype "passive"))
      (node (ref "U1") (pin "L11") (pinfunction "VDD_L11") (pintype "passive"))
      (node (ref "U1") (pin "L13") (pinfunction "VDD_L13") (pintype "passive"))
      (node (ref "U1") (pin "L15") (pinfunction "VDD_L15") (pintype "passive"))
      (node (ref "U1") (pin "L17") (pinfunction "VDD_L17") (pintype "passive"))
      (node (ref "U1") (pin "L19") (pinfunction "VDD_L19") (pintype "passive"))
      (node (ref "U1") (pin "L21") (pinfunction "VDD_L21") (pintype "passive"))
      (node (ref "U1") (pin "L3") (pinfunction "VDD_L3") (pintype "passive"))
      (node (ref "U1") (pin "L5") (pinfunction "VDD_L5") (pintype "passive"))
      (node (ref "U1") (pin "L7") (pinfunction "VDD_L7") (pintype "passive"))
      (node (ref "U1") (pin "L9") (pinfunction "VDD_L9") (pintype "passive"))
      (node (ref "U1") (pin "M10") (pinfunction "VDD_M10") (pintype "passive"))
      (node (ref "U1") (pin "M12") (pinfunction "VDD_M12") (pintype "passive"))
      (node (ref "U1") (pin "M14") (pinfunction "VDD_M14") (pintype "passive"))
      (node (ref "U1") (pin "M16") (pinfunction "VDD_M16") (pintype "passive"))
      (node (ref "U1") (pin "M18") (pinfunction "VDD_M18") (pintype "passive"))
      (node (ref "U1") (pin "M2") (pinfunction "VDD_M2") (pintype "passive"))
      (node (ref "U1") (pin "M4") (pinfunction "VDD_M4") (pintype "passive"))
      (node (ref "U1") (pin "M6") (pinfunction "VDD_M6") (pintype "passive"))
      (node (ref "U1") (pin "M8") (pinfunction "VDD_M8") (pintype "passive"))
      (node (ref "U1") (pin "N1") (pinfunction "VDD_N1") (pintype "passive"))
      (node (ref "U1") (pin "N11") (pinfunction "VDD_N11") (pintype "passive"))
      (node (ref "U1") (pin "N13") (pinfunction "VDD_N13") (pintype "passive"))
      (node (ref "U1") (pin "N15") (pinfunction "VDD_N15") (pintype "passive"))
      (node (ref "U1") (pin "N17") (pinfunction "VDD_N17") (pintype "passive"))
      (node (ref "U1") (pin "N19") (pinfunction "VDD_N19") (pintype "passive"))
      (node (ref "U1") (pin "N21") (pinfunction "VDD_N21") (pintype "passive"))
      (node (ref "U1") (pin "N3") (pinfunction "VDD_N3") (pintype "passive"))
      (node (ref "U1") (pin "N5") (pinfunction "VDD_N5") (pintype "passive"))
      (node (ref "U1") (pin "N7") (pinfunction "VDD_N7") (pintype "passive"))
      (node (ref "U1") (pin "N9") (pinfunction "VDD_N9") (pintype "passive"))
      (node (ref "U1") (pin "P10") (pinfunction "VDD_P10") (pintype "passive"))
      (node (ref "U1") (pin "P12") (pinfunction "VDD_P12") (pintype "passive"))
      (node (ref "U1") (pin "P14") (pinfunction "VDD_P14") (pintype "passive"))
      (node (ref "U1") (pin "P16") (pinfunction "VDD_P16") (pintype "passive"))
      (node (ref "U1") (pin "P18") (pinfunction "VDD_P18") (pintype "passive"))
      (node (ref "U1") (pin "P2") (pinfunction "VDD_P2") (pintype "passive"))
      (node (ref "U1") (pin "P20") (pinfunction "VDD_P20") (pintype "passive"))
      (node (ref "U1") (pin "P4") (pinfunction "VDD_P4") (pintype "passive"))
      (node (ref "U1") (pin "P6") (pinfunction "VDD_P6") (pintype "passive"))
      (node (ref "U1") (pin "P8") (pinfunction "VDD_P8") (pintype "passive"))
      (node (ref "U1") (pin "R1") (pinfunction "VDD_R1") (pintype "passive"))
      (node (ref "U1") (pin "R11") (pinfunction "VDD_R11") (pintype "passive"))
      (node (ref "U1") (pin "R13") (pinfunction "VDD_R13") (pintype "passive"))
      (node (ref "U1") (pin "R15") (pinfunction "VDD_R15") (pintype "passive"))
      (node (ref "U1") (pin "R17") (pinfunction "VDD_R17") (pintype "passive"))
      (node (ref "U1") (pin "R19") (pinfunction "VDD_R19") (pintype "passive"))
      (node (ref "U1") (pin "R21") (pinfunction "VDD_R21") (pintype "passive"))
      (node (ref "U1") (pin "R3") (pinfunction "VDD_R3") (pintype "passive"))
      (node (ref "U1") (pin "R5") (pinfunction "VDD_R5") (pintype "passive"))
      (node (ref "U1") (pin "R7") (pinfunction "VDD_R7") (pintype "passive"))
      (node (ref "U1") (pin "R9") (pinfunction "VDD_R9") (pintype "passive"))
      (node (ref "U1") (pin "T10") (pinfunction "VDD_T10") (pintype "passive"))
      (node (ref "U1") (pin "T12") (pinfunction "VDD_T12") (pintype "passive"))
      (node (ref "U1") (pin "T14") (pinfunction "VDD_T14") (pintype "passive"))
      (node (ref "U1") (pin "T16") (pinfunction "VDD_T16") (pintype "passive"))
      (node (ref "U1") (pin "T18") (pinfunction "VDD_T18") (pintype "passive"))
      (node (ref "U1") (pin "T2") (pinfunction "VDD_T2") (pintype "passive"))
      (node (ref "U1") (pin "T20") (pinfunction "VDD_T20") (pintype "passive"))
      (node (ref "U1") (pin "T4") (pinfunction "VDD_T4") (pintype "passive"))
      (node (ref "U1") (pin "T6") (pinfunction "VDD_T6") (pintype "passive"))
      (node (ref "U1") (pin "T8") (pinfunction "VDD_T8") (pintype "passive"))
      (node (ref "U1") (pin "U1") (pinfunction "VDD_U1") (pintype "passive"))
      (node (ref "U1") (pin "U11") (pinfunction "VDD_U11") (pintype "passive"))
      (node (ref "U1") (pin "U13") (pinfunction "VDD_U13") (pintype "passive"))
      (node (ref "U1") (pin "U15") (pinfunction "VDD_U15") (pintype "passive"))
      (node (ref "U1") (pin "U17") (pinfunction "VDD_U17") (pintype "passive"))
      (node (ref "U1") (pin "U19") (pinfunction "VDD_U19") (pintype "passive"))
      (node (ref "U1") (pin "U21") (pinfunction "VDD_U21") (pintype "passive"))
      (node (ref "U1") (pin "U3") (pinfunction "VDD_U3") (pintype "passive"))
      (node (ref "U1") (pin "U5") (pinfunction "VDD_U5") (pintype "passive"))
      (node (ref "U1") (pin "U7") (pinfunction "VDD_U7") (pintype "passive"))
      (node (ref "U1") (pin "U9") (pinfunction "VDD_U9") (pintype "passive"))
      (node (ref "U1") (pin "V10") (pinfunction "VDD_V10") (pintype "passive"))
      (node (ref "U1") (pin "V12") (pinfunction "VDD_V12") (pintype "passive"))
      (node (ref "U1") (pin "V14") (pinfunction "VDD_V14") (pintype "passive"))
      (node (ref "U1") (pin "V16") (pinfunction "VDD_V16") (pintype "passive"))
      (node (ref "U1") (pin "V18") (pinfunction "VDD_V18") (pintype "passive"))
      (node (ref "U1") (pin "V2") (pinfunction "VDD_V2") (pintype "passive"))
      (node (ref "U1") (pin "V20") (pinfunction "VDD_V20") (pintype "passive"))
      (node (ref "U1") (pin "V4") (pinfunction "VDD_V4") (pintype "passive"))
      (node (ref "U1") (pin "V6") (pinfunction "VDD_V6") (pintype "passive"))
      (node (ref "U1") (pin "V8") (pinfunction "VDD_V8") (pintype "passive"))
      (node (ref "U1") (pin "W1") (pinfunction "VDD_W1") (pintype "passive"))
      (node (ref "U1") (pin "W11") (pinfunction "VDD_W11") (pintype "passive"))
      (node (ref "U1") (pin "W13") (pinfunction "VDD_W13") (pintype "passive"))
      (node (ref "U1") (pin "W15") (pinfunction "VDD_W15") (pintype "passive"))
      (node (ref "U1") (pin "W17") (pinfunction "VDD_W17") (pintype "passive"))
      (node (ref "U1") (pin "W19") (pinfunction "VDD_W19") (pintype "passive"))
      (node (ref "U1") (pin "W21") (pinfunction "VDD_W21") (pintype "passive"))
      (node (ref "U1") (pin "W3") (pinfunction "VDD_W3") (pintype "passive"))
      (node (ref "U1") (pin "W5") (pinfunction "VDD_W5") (pintype "passive"))
      (node (ref "U1") (pin "W7") (pinfunction "VDD_W7") (pintype "passive"))
      (node (ref "U1") (pin "W9") (pinfunction "VDD_W9") (pintype "passive"))
      (node (ref "U1") (pin "Y10") (pinfunction "VDD_Y10") (pintype "passive"))
      (node (ref "U1") (pin "Y12") (pinfunction "VDD_Y12") (pintype "passive"))
      (node (ref "U1") (pin "Y14") (pinfunction "VDD_Y14") (pintype "passive"))
      (node (ref "U1") (pin "Y16") (pinfunction "VDD_Y16") (pintype "passive"))
      (node (ref "U1") (pin "Y18") (pinfunction "VDD_Y18") (pintype "passive"))
      (node (ref "U1") (pin "Y2") (pinfunction "VDD_Y2") (pintype "passive"))
      (node (ref "U1") (pin "Y20") (pinfunction "VDD_Y20") (pintype "passive"))
      (node (ref "U1") (pin "Y4") (pinfunction "VDD_Y4") (pintype "passive"))
      (node (ref "U1") (pin "Y6") (pinfunction "VDD_Y6") (pintype "passive"))
      (node (ref "U1") (pin "Y8") (pinfunction "VDD_Y8") (pintype "passive"))
    )
    (net (code "2") (name "GND") (class "Default")
      (node (ref "C1") (pin "1") (pinfunction "1_1") (pintype "passive"))
      (node (ref "C148") (pin "1") (pinfunction "1_1") (pintype "passive"))
      (node (ref "C149") (pin "1") (pinfunction "1_1") (pintype "passive"))
      (node (ref "C150") (pin "1") (pinfunction "1_1") (pintype "passive"))
      (node (ref "C151") (pin "1") (pinfunction "1_1") (pintype "passive"))
      (node (ref "C152") (pin "1") (pinfunction "1_1") (pintype "passive"))
      (node (ref "C153") (pin "1") (pinfunction "1_1") (pintype "passive"))
      (node (ref "C154") (pin "1") (pinfunction "1_1") (pintype "passive"))
      (node (ref "C155") (pin "1") (pinfunction "1_1") (pintype "passive"))
      (node (ref "C156") (pin "1") (pinfunction "1_1") (pintype "passive"))
      (node (ref "C157") (pin "1") (pinfunction "1_1") (pintype "passive"))
      (node (ref "C158") (pin "1") (pinfunction "1_1") (pintype "passive"))
      (node (ref "C159") (pin "1") (pinfunction "1_1") (pintype "passive"))
      (node (ref "C160") (pin "1") (pinfunction "1_1") (pintype "passive"))
      (node (ref "C161") (pin "1") (pinfunction "1_1") (pintype "passive"))
      (node (ref "C162") (pin "1") (pinfunction "1_1") (pintype "passive"))
      (node (ref "C163") (pin "1") (pinfunction "1_1") (pintype "passive"))
      (node (ref "C164") (pin "1") (pinfunction "1_1") (pintype "passive"))
      (node (ref "C165") (pin "1") (pinfunction "1_1") (pintype "passive"))
      (node (ref "C168") (pin "1") (pinfunction "1_1") (pintype "passive"))
      (node (ref "C177") (pin "1") (pinfunction "1_1") (pintype "passive"))
      (node (ref "C178") (pin "1") (pinfunction "1_1") (pintype "passive"))
      (node (ref "C179") (pin "1") (pinfunction "1_1") (pintype "passive"))
      (node (ref "C18") (pin "1") (pinfunction "1_1") (pintype "passive"))
      (node (ref "C180") (pin "1") (pinfunction "1_1") (pintype "passive"))
      (node (ref "C181") (pin "1") (pinfunction "1_1") (pintype "passive"))
      (node (ref "C182") (pin "1") (pinfunction "1_1") (pintype "passive"))
      (node (ref "C183") (pin "1") (pinfunction "1_1") (pintype "passive"))
      (node (ref "C184") (pin "1") (pinfunction "1_1") (pintype "passive"))
      (node (ref "C185") (pin "1") (pinfunction "1_1") (pintype "passive"))
      (node (ref "C186") (pin "1") (pinfunction "1_1") (pintype "passive"))
      (node (ref "C19") (pin "1") (pinfunction "1_1") (pintype "passive"))
      (node (ref "C206") (pin "1") (pinfunction "1_1") (pintype "passive"))
      (node (ref "C207") (pin "1") (pinfunction "1_1") (pintype "passive"))
      (node (ref "C208") (pin "1") (pinfunction "1_1") (pintype "passive"))
      (node (ref "C209") (pin "1") (pinfunction "1_1") (pintype "passive"))
      (node (ref "C210") (pin "1") (pinfunction "1_1") (pintype "passive"))
      (node (ref "C211") (pin "1") (pinfunction "1_1") (pintype "passive"))
      (node (ref "C212") (pin "1") (pinfunction "1_1") (pintype "passive"))
      (node (ref "C213") (pin "1") (pinfunction "1_1") (pintype "passive"))
      (node (ref "C214") (pin "1") (pinfunction "1_1") (pintype "passive"))
      (node (ref "C215") (pin "1") (pinfunction "1_1") (pintype "passive"))
      (node (ref "C216") (pin "1") (pinfunction "1_1") (pintype "passive"))
      (node (ref "C217") (pin "1") (pinfunction "1_1") (pintype "passive"))
      (node (ref "C218") (pin "1") (pinfunction "1_1") (pintype "passive"))
      (node (ref "C219") (pin "1") (pinfunction "1_1") (pintype "passive"))
      (node (ref "C220") (pin "1") (pinfunction "1_1") (pintype "passive"))
      (node (ref "C221") (pin "1") (pinfunction "1_1") (pintype "passive"))
      (node (ref "C222") (pin "1") (pinfunction "1_1") (pintype "passive"))
      (node (ref "C223") (pin "1") (pinfunction "1_1") (pintype "passive"))
      (node (ref "C224") (pin "1") (pinfunction "1_1") (pintype "passive"))
      (node (ref "C225") (pin "1") (pinfunction "1_1") (pintype "passive"))
      (node (ref "C226") (pin "1") (pinfunction "1_1") (pintype "passive"))
      (node (ref "C228") (pin "1") (pinfunction "1_1") (pintype "passive"))
      (node (ref "C229") (pin "1") (pinfunction "1_1") (pintype "passive"))
      (node (ref "C230") (pin "1") (pinfunction "1_1") (pintype "passive"))
      (node (ref "C234") (pin "1") (pinfunction "1_1") (pintype "passive"))
      (node (ref "C235") (pin "1") (pinfunction "1_1") (pintype "passive"))
      (node (ref "C236") (pin "1") (pinfunction "1_1") (pintype "passive"))
      (node (ref "C237") (pin "1") (pinfunction "1_1") (pintype "passive"))
      (node (ref "C238") (pin "1") (pinfunction "1_1") (pintype "passive"))
      (node (ref "C239") (pin "1") (pinfunction "1_1") (pintype "passive"))
      (node (ref "C240") (pin "1") (pinfunction "1_1") (pintype "passive"))
      (node (ref "C241") (pin "1") (pinfunction "1_1") (pintype "passive"))
      (node (ref "C242") (pin "1") (pinfunction "1_1") (pintype "passive"))
      (node (ref "C243") (pin "1") (pinfunction "1_1") (pintype "passive"))
      (node (ref "C244") (pin "1") (pinfunction "1_1") (pintype "passive"))
      (node (ref "C245") (pin "1") (pinfunction "1_1") (pintype "passive"))
      (node (ref "C246") (pin "1") (pinfunction "1_1") (pintype "passive"))
      (node (ref "C247") (pin "1") (pinfunction "1_1") (pintype "passive"))
      (node (ref "C248") (pin "1") (pinfunction "1_1") (pintype "passive"))
      (node (ref "C249") (pin "1") (pinfunction "1_1") (pintype "passive"))
      (node (ref "C250") (pin "1") (pinfunction "1_1") (pintype "passive"))
      (node (ref "C251") (pin "1") (pinfunction "1_1") (pintype "passive"))
      (node (ref "C252") (pin "1") (pinfunction "1_1") (pintype "passive"))
      (node (ref "C253") (pin "1") (pinfunction "1_1") (pintype "passive"))
      (node (ref "C254") (pin "1") (pinfunction "1_1") (pintype "passive"))
      (node (ref "C255") (pin "1") (pinfunction "1_1") (pintype "passive"))
      (node (ref "C256") (pin "1") (pinfunction "1_1") (pintype "passive"))
      (node (ref "C36") (pin "1") (pinfunction "1_1") (pintype "passive"))
      (node (ref "C62") (pin "1") (pinfunction "1_1") (pintype "passive"))
      (node (ref "C63") (pin "1") (pinfunction "1_1") (pintype "passive"))
      (node (ref "C74") (pin "1") (pinfunction "1_1") (pintype "passive"))
      (node (ref "C75") (pin "1") (pinfunction "1_1") (pintype "passive"))
      (node (ref "C76") (pin "1") (pinfunction "1_1") (pintype "passive"))
      (node (ref "C77") (pin "1") (pinfunction "1_1") (pintype "passive"))
      (node (ref "C78") (pin "1") (pinfunction "1_1") (pintype "passive"))
      (node (ref "C79") (pin "1") (pinfunction "1_1") (pintype "passive"))
      (node (ref "C80") (pin "1") (pinfunction "1_1") (pintype "passive"))
      (node (ref "C81") (pin "1") (pinfunction "1_1") (pintype "passive"))
      (node (ref "U1") (pin "A10") (pinfunction "VSS_A10") (pintype "passive"))
      (node (ref "U1") (pin "A12") (pinfunction "VSS_A12") (pintype "passive"))
      (node (ref "U1") (pin "A14") (pinfunction "VSS_A14") (pintype "passive"))
      (node (ref "U1") (pin "A16") (pinfunction "VSS_A16") (pintype "passive"))
      (node (ref "U1") (pin "A18") (pinfunction "VSS_A18") (pintype "passive"))
      (node (ref "U1") (pin "A2") (pinfunction "VSS_A2") (pintype "passive"))
      (node (ref "U1") (pin "A20") (pinfunction "VSS_A20") (pintype "passive"))
      (node (ref "U1") (pin "A4") (pinfunction "VSS_A4") (pintype "passive"))
      (node (ref "U1") (pin "A6") (pinfunction "VSS_A6") (pintype "passive"))
      (node (ref "U1") (pin "A8") (pinfunction "VSS_A8") (pintype "passive"))
      (node (ref "U1") (pin "AA10") (pinfunction "VSS_AA10") (pintype "passive"))
      (node (ref "U1") (pin "AA12") (pinfunction "VSS_AA12") (pintype "passive"))
      (node (ref "U1") (pin "AA14") (pinfunction "VSS_AA14") (pintype "passive"))
      (node (ref "U1") (pin "AA16") (pinfunction "VSS_AA16") (pintype "passive"))
      (node (ref "U1") (pin "AA18") (pinfunction "VSS_AA18") (pintype "passive"))
      (node (ref "U1") (pin "AA2") (pinfunction "VSS_AA2") (pintype "passive"))
      (node (ref "U1") (pin "AA4") (pinfunction "VSS_AA4") (pintype "passive"))
      (node (ref "U1") (pin "AA6") (pinfunction "VSS_AA6") (pintype "passive"))
      (node (ref "U1") (pin "AA8") (pinfunction "VSS_AA8") (pintype "passive"))
      (node (ref "U1") (pin "AB11") (pinfunction "VSS_AB11") (pintype "passive"))
      (node (ref "U1") (pin "AB13") (pinfunction "VSS_AB13") (pintype "passive"))
      (node (ref "U1") (pin "AB15") (pinfunction "VSS_AB15") (pintype "passive"))
      (node (ref "U1") (pin "AB17") (pinfunction "VSS_AB17") (pintype "passive"))
      (node (ref "U1") (pin "AB3") (pinfunction "VSS_AB3") (pintype "passive"))
      (node (ref "U1") (pin "AB5") (pinfunction "VSS_AB5") (pintype "passive"))
      (node (ref "U1") (pin "AB7") (pinfunction "VSS_AB7") (pintype "passive"))
      (node (ref "U1") (pin "AB9") (pinfunction "VSS_AB9") (pintype "passive"))
      (node (ref "U1") (pin "B1") (pinfunction "VSS_B1") (pintype "passive"))
      (node (ref "U1") (pin "B11") (pinfunction "VSS_B11") (pintype "passive"))
      (node (ref "U1") (pin "B13") (pinfunction "VSS_B13") (pintype "passive"))
      (node (ref "U1") (pin "B15") (pinfunction "VSS_B15") (pintype "passive"))
      (node (ref "U1") (pin "B17") (pinfunction "VSS_B17") (pintype "passive"))
      (node (ref "U1") (pin "B19") (pinfunction "VSS_B19") (pintype "passive"))
      (node (ref "U1") (pin "B21") (pinfunction "VSS_B21") (pintype "passive"))
      (node (ref "U1") (pin "B22") (pinfunction "VSS_B22") (pintype "passive"))
      (node (ref "U1") (pin "B3") (pinfunction "VSS_B3") (pintype "passive"))
      (node (ref "U1") (pin "B5") (pinfunction "VSS_B5") (pintype "passive"))
      (node (ref "U1") (pin "B7") (pinfunction "VSS_B7") (pintype "passive"))
      (node (ref "U1") (pin "B9") (pinfunction "VSS_B9") (pintype "passive"))
      (node (ref "U1") (pin "C10") (pinfunction "VSS_C10") (pintype "passive"))
      (node (ref "U1") (pin "C12") (pinfunction "VSS_C12") (pintype "passive"))
      (node (ref "U1") (pin "C14") (pinfunction "VSS_C14") (pintype "passive"))
      (node (ref "U1") (pin "C16") (pinfunction "VSS_C16") (pintype "passive"))
      (node (ref "U1") (pin "C18") (pinfunction "VSS_C18") (pintype "passive"))
      (node (ref "U1") (pin "C2") (pinfunction "VSS_C2") (pintype "passive"))
      (node (ref "U1") (pin "C20") (pinfunction "VSS_C20") (pintype "passive"))
      (node (ref "U1") (pin "C4") (pinfunction "VSS_C4") (pintype "passive"))
      (node (ref "U1") (pin "C6") (pinfunction "VSS_C6") (pintype "passive"))
      (node (ref "U1") (pin "C8") (pinfunction "VSS_C8") (pintype "passive"))
      (node (ref "U1") (pin "D1") (pinfunction "VSS_D1") (pintype "passive"))
      (node (ref "U1") (pin "D11") (pinfunction "VSS_D11") (pintype "passive"))
      (node (ref "U1") (pin "D13") (pinfunction "VSS_D13") (pintype "passive"))
      (node (ref "U1") (pin "D15") (pinfunction "VSS_D15") (pintype "passive"))
      (node (ref "U1") (pin "D17") (pinfunction "VSS_D17") (pintype "passive"))
      (node (ref "U1") (pin "D19") (pinfunction "VSS_D19") (pintype "passive"))
      (node (ref "U1") (pin "D21") (pinfunction "VSS_D21") (pintype "passive"))
      (node (ref "U1") (pin "D22") (pinfunction "VSS_D22") (pintype "passive"))
      (node (ref "U1") (pin "D3") (pinfunction "VSS_D3") (pintype "passive"))
      (node (ref "U1") (pin "D5") (pinfunction "VSS_D5") (pintype "passive"))
      (node (ref "U1") (pin "D7") (pinfunction "VSS_D7") (pintype "passive"))
      (node (ref "U1") (pin "D9") (pinfunction "VSS_D9") (pintype "passive"))
      (node (ref "U1") (pin "E10") (pinfunction "VSS_E10") (pintype "passive"))
      (node (ref "U1") (pin "E12") (pinfunction "VSS_E12") (pintype "passive"))
      (node (ref "U1") (pin "E14") (pinfunction "VSS_E14") (pintype "passive"))
      (node (ref "U1") (pin "E16") (pinfunction "VSS_E16") (pintype "passive"))
      (node (ref "U1") (pin "E18") (pinfunction "VSS_E18") (pintype "passive"))
      (node (ref "U1") (pin "E2") (pinfunction "VSS_E2") (pintype "passive"))
      (node (ref "U1") (pin "E20") (pinfunction "VSS_E20") (pintype "passive"))
      (node (ref "U1") (pin "E4") (pinfunction "VSS_E4") (pintype "passive"))
      (node (ref "U1") (pin "E6") (pinfunction "VSS_E6") (pintype "passive"))
      (node (ref "U1") (pin "E8") (pinfunction "VSS_E8") (pintype "passive"))
      (node (ref "U1") (pin "F1") (pinfunction "VSS_F1") (pintype "passive"))
      (node (ref "U1") (pin "F11") (pinfunction "VSS_F11") (pintype "passive"))
      (node (ref "U1") (pin "F13") (pinfunction "VSS_F13") (pintype "passive"))
      (node (ref "U1") (pin "F15") (pinfunction "VSS_F15") (pintype "passive"))
      (node (ref "U1") (pin "F17") (pinfunction "VSS_F17") (pintype "passive"))
      (node (ref "U1") (pin "F19") (pinfunction "VSS_F19") (pintype "passive"))
      (node (ref "U1") (pin "F21") (pinfunction "VSS_F21") (pintype "passive"))
      (node (ref "U1") (pin "F22") (pinfunction "VSS_F22") (pintype "passive"))
      (node (ref "U1") (pin "F3") (pinfunction "VSS_F3") (pintype "passive"))
      (node (ref "U1") (pin "F5") (pinfunction "VSS_F5") (pintype "passive"))
      (node (ref "U1") (pin "F7") (pinfunction "VSS_F7") (pintype "passive"))
      (node (ref "U1") (pin "F9") (pinfunction "VSS_F9") (pintype "passive"))
      (node (ref "U1") (pin "G10") (pinfunction "VSS_G10") (pintype "passive"))
      (node (ref "U1") (pin "G12") (pinfunction "VSS_G12") (pintype "passive"))
      (node (ref "U1") (pin "G14") (pinfunction "VSS_G14") (pintype "passive"))
      (node (ref "U1") (pin "G16") (pinfunction "VSS_G16") (pintype "passive"))
      (node (ref "U1") (pin "G18") (pinfunction "VSS_G18") (pintype "passive"))
      (node (ref "U1") (pin "G2") (pinfunction "VSS_G2") (pintype "passive"))
      (node (ref "U1") (pin "G20") (pinfunction "VSS_G20") (pintype "passive"))
      (node (ref "U1") (pin "G4") (pinfunction "VSS_G4") (pintype "passive"))
      (node (ref "U1") (pin "G6") (pinfunction "VSS_G6") (pintype "passive"))
      (node (ref "U1") (pin "G8") (pinfunction "VSS_G8") (pintype "passive"))
      (node (ref "U1") (pin "H1") (pinfunction "VSS_H1") (pintype "passive"))
      (node (ref "U1") (pin "H11") (pinfunction "VSS_H11") (pintype "passive"))
      (node (ref "U1") (pin "H13") (pinfunction "VSS_H13") (pintype "passive"))
      (node (ref "U1") (pin "H15") (pinfunction "VSS_H15") (pintype "passive"))
      (node (ref "U1") (pin "H17") (pinfunction "VSS_H17") (pintype "passive"))
      (node (ref "U1") (pin "H19") (pinfunction "VSS_H19") (pintype "passive"))
      (node (ref "U1") (pin "H21") (pinfunction "VSS_H21") (pintype "passive"))
      (node (ref "U1") (pin "H22") (pinfunction "VSS_H22") (pintype "passive"))
      (node (ref "U1") (pin "H3") (pinfunction "VSS_H3") (pintype "passive"))
      (node (ref "U1") (pin "H5") (pinfunction "VSS_H5") (pintype "passive"))
      (node (ref "U1") (pin "H7") (pinfunction "VSS_H7") (pintype "passive"))
      (node (ref "U1") (pin "H9") (pinfunction "VSS_H9") (pintype "passive"))
      (node (ref "U1") (pin "J10") (pinfunction "VSS_J10") (pintype "passive"))
      (node (ref "U1") (pin "J12") (pinfunction "VSS_J12") (pintype "passive"))
      (node (ref "U1") (pin "J14") (pinfunction "VSS_J14") (pintype "passive"))
      (node (ref "U1") (pin "J16") (pinfunction "VSS_J16") (pintype "passive"))
      (node (ref "U1") (pin "J18") (pinfunction "VSS_J18") (pintype "passive"))
      (node (ref "U1") (pin "J2") (pinfunction "VSS_J2") (pintype "passive"))
      (node (ref "U1") (pin "J20") (pinfunction "VSS_J20") (pintype "passive"))
      (node (ref "U1") (pin "J4") (pinfunction "VSS_J4") (pintype "passive"))
      (node (ref "U1") (pin "J6") (pinfunction "VSS_J6") (pintype "passive"))
      (node (ref "U1") (pin "J8") (pinfunction "VSS_J8") (pintype "passive"))
      (node (ref "U1") (pin "K1") (pinfunction "VSS_K1") (pintype "passive"))
      (node (ref "U1") (pin "K11") (pinfunction "VSS_K11") (pintype "passive"))
      (node (ref "U1") (pin "K13") (pinfunction "VSS_K13") (pintype "passive"))
      (node (ref "U1") (pin "K15") (pinfunction "VSS_K15") (pintype "passive"))
      (node (ref "U1") (pin "K17") (pinfunction "VSS_K17") (pintype "passive"))
      (node (ref "U1") (pin "K19") (pinfunction "VSS_K19") (pintype "passive"))
      (node (ref "U1") (pin "K21") (pinfunction "VSS_K21") (pintype "passive"))
      (node (ref "U1") (pin "K22") (pinfunction "VSS_K22") (pintype "passive"))
      (node (ref "U1") (pin "K3") (pinfunction "VSS_K3") (pintype "passive"))
      (node (ref "U1") (pin "K5") (pinfunction "VSS_K5") (pintype "passive"))
      (node (ref "U1") (pin "K7") (pinfunction "VSS_K7") (pintype "passive"))
      (node (ref "U1") (pin "K9") (pinfunction "VSS_K9") (pintype "passive"))
      (node (ref "U1") (pin "L10") (pinfunction "VSS_L10") (pintype "passive"))
      (node (ref "U1") (pin "L12") (pinfunction "VSS_L12") (pintype "passive"))
      (node (ref "U1") (pin "L14") (pinfunction "VSS_L14") (pintype "passive"))
      (node (ref "U1") (pin "L16") (pinfunction "VSS_L16") (pintype "passive"))
      (node (ref "U1") (pin "L18") (pinfunction "VSS_L18") (pintype "passive"))
      (node (ref "U1") (pin "L2") (pinfunction "VSS_L2") (pintype "passive"))
      (node (ref "U1") (pin "L20") (pinfunction "VSS_L20") (pintype "passive"))
      (node (ref "U1") (pin "L4") (pinfunction "VSS_L4") (pintype "passive"))
      (node (ref "U1") (pin "L6") (pinfunction "VSS_L6") (pintype "passive"))
      (node (ref "U1") (pin "L8") (pinfunction "VSS_L8") (pintype "passive"))
      (node (ref "U1") (pin "M1") (pinfunction "VSS_M1") (pintype "passive"))
      (node (ref "U1") (pin "M11") (pinfunction "VSS_M11") (pintype "passive"))
      (node (ref "U1") (pin "M13") (pinfunction "VSS_M13") (pintype "passive"))
      (node (ref "U1") (pin "M15") (pinfunction "VSS_M15") (pintype "passive"))
      (node (ref "U1") (pin "M17") (pinfunction "VSS_M17") (pintype "passive"))
      (node (ref "U1") (pin "M19") (pinfunction "VSS_M19") (pintype "passive"))
      (node (ref "U1") (pin "M21") (pinfunction "VSS_M21") (pintype "passive"))
      (node (ref "U1") (pin "M3") (pinfunction "VSS_M3") (pintype "passive"))
      (node (ref "U1") (pin "M5") (pinfunction "VSS_M5") (pintype "passive"))
      (node (ref "U1") (pin "M7") (pinfunction "VSS_M7") (pintype "passive"))
      (node (ref "U1") (pin "M9") (pinfunction "VSS_M9") (pintype "passive"))
      (node (ref "U1") (pin "N10") (pinfunction "VSS_N10") (pintype "passive"))
      (node (ref "U1") (pin "N12") (pinfunction "VSS_N12") (pintype "passive"))
      (node (ref "U1") (pin "N14") (pinfunction "VSS_N14") (pintype "passive"))
      (node (ref "U1") (pin "N16") (pinfunction "VSS_N16") (pintype "passive"))
      (node (ref "U1") (pin "N18") (pinfunction "VSS_N18") (pintype "passive"))
      (node (ref "U1") (pin "N2") (pinfunction "VSS_N2") (pintype "passive"))
      (node (ref "U1") (pin "N4") (pinfunction "VSS_N4") (pintype "passive"))
      (node (ref "U1") (pin "N6") (pinfunction "VSS_N6") (pintype "passive"))
      (node (ref "U1") (pin "N8") (pinfunction "VSS_N8") (pintype "passive"))
      (node (ref "U1") (pin "P1") (pinfunction "VSS_P1") (pintype "passive"))
      (node (ref "U1") (pin "P11") (pinfunction "VSS_P11") (pintype "passive"))
      (node (ref "U1") (pin "P13") (pinfunction "VSS_P13") (pintype "passive"))
      (node (ref "U1") (pin "P15") (pinfunction "VSS_P15") (pintype "passive"))
      (node (ref "U1") (pin "P17") (pinfunction "VSS_P17") (pintype "passive"))
      (node (ref "U1") (pin "P19") (pinfunction "VSS_P19") (pintype "passive"))
      (node (ref "U1") (pin "P21") (pinfunction "VSS_P21") (pintype "passive"))
      (node (ref "U1") (pin "P22") (pinfunction "VSS_P22") (pintype "passive"))
      (node (ref "U1") (pin "P3") (pinfunction "VSS_P3") (pintype "passive"))
      (node (ref "U1") (pin "P5") (pinfunction "VSS_P5") (pintype "passive"))
      (node (ref "U1") (pin "P7") (pinfunction "VSS_P7") (pintype "passive"))
      (node (ref "U1") (pin "P9") (pinfunction "VSS_P9") (pintype "passive"))
      (node (ref "U1") (pin "R10") (pinfunction "VSS_R10") (pintype "passive"))
      (node (ref "U1") (pin "R12") (pinfunction "VSS_R12") (pintype "passive"))
      (node (ref "U1") (pin "R14") (pinfunction "VSS_R14") (pintype "passive"))
      (node (ref "U1") (pin "R16") (pinfunction "VSS_R16") (pintype "passive"))
      (node (ref "U1") (pin "R18") (pinfunction "VSS_R18") (pintype "passive"))
      (node (ref "U1") (pin "R2") (pinfunction "VSS_R2") (pintype "passive"))
      (node (ref "U1") (pin "R20") (pinfunction "VSS_R20") (pintype "passive"))
      (node (ref "U1") (pin "R4") (pinfunction "VSS_R4") (pintype "passive"))
      (node (ref "U1") (pin "R6") (pinfunction "VSS_R6") (pintype "passive"))
      (node (ref "U1") (pin "R8") (pinfunction "VSS_R8") (pintype "passive"))
      (node (ref "U1") (pin "T1") (pinfunction "VSS_T1") (pintype "passive"))
      (node (ref "U1") (pin "T11") (pinfunction "VSS_T11") (pintype "passive"))
      (node (ref "U1") (pin "T13") (pinfunction "VSS_T13") (pintype "passive"))
      (node (ref "U1") (pin "T15") (pinfunction "VSS_T15") (pintype "passive"))
      (node (ref "U1") (pin "T17") (pinfunction "VSS_T17") (pintype "passive"))
      (node (ref "U1") (pin "T19") (pinfunction "VSS_T19") (pintype "passive"))
      (node (ref "U1") (pin "T21") (pinfunction "VSS_T21") (pintype "passive"))
      (node (ref "U1") (pin "T22") (pinfunction "VSS_T22") (pintype "passive"))
      (node (ref "U1") (pin "T3") (pinfunction "VSS_T3") (pintype "passive"))
      (node (ref "U1") (pin "T5") (pinfunction "VSS_T5") (pintype "passive"))
      (node (ref "U1") (pin "T7") (pinfunction "VSS_T7") (pintype "passive"))
      (node (ref "U1") (pin "T9") (pinfunction "VSS_T9") (pintype "passive"))
      (node (ref "U1") (pin "U10") (pinfunction "VSS_U10") (pintype "passive"))
      (node (ref "U1") (pin "U12") (pinfunction "VSS_U12") (pintype "passive"))
      (node (ref "U1") (pin "U14") (pinfunction "VSS_U14") (pintype "passive"))
      (node (ref "U1") (pin "U16") (pinfunction "VSS_U16") (pintype "passive"))
      (node (ref "U1") (pin "U18") (pinfunction "VSS_U18") (pintype "passive"))
      (node (ref "U1") (pin "U2") (pinfunction "VSS_U2") (pintype "passive"))
      (node (ref "U1") (pin "U20") (pinfunction "VSS_U20") (pintype "passive"))
      (node (ref "U1") (pin "U4") (pinfunction "VSS_U4") (pintype "passive"))
      (node (ref "U1") (pin "U6") (pinfunction "VSS_U6") (pintype "passive"))
      (node (ref "U1") (pin "U8") (pinfunction "VSS_U8") (pintype "passive"))
      (node (ref "U1") (pin "V1") (pinfunction "VSS_V1") (pintype "passive"))
      (node (ref "U1") (pin "V11") (pinfunction "VSS_V11") (pintype "passive"))
      (node (ref "U1") (pin "V13") (pinfunction "VSS_V13") (pintype "passive"))
      (node (ref "U1") (pin "V15") (pinfunction "VSS_V15") (pintype "passive"))
      (node (ref "U1") (pin "V17") (pinfunction "VSS_V17") (pintype "passive"))
      (node (ref "U1") (pin "V19") (pinfunction "VSS_V19") (pintype "passive"))
      (node (ref "U1") (pin "V21") (pinfunction "VSS_V21") (pintype "passive"))
      (node (ref "U1") (pin "V22") (pinfunction "VSS_V22") (pintype "passive"))
      (node (ref "U1") (pin "V3") (pinfunction "VSS_V3") (pintype "passive"))
      (node (ref "U1") (pin "V5") (pinfunction "VSS_V5") (pintype "passive"))
      (node (ref "U1") (pin "V7") (pinfunction "VSS_V7") (pintype "passive"))
      (node (ref "U1") (pin "V9") (pinfunction "VSS_V9") (pintype "passive"))
      (node (ref "U1") (pin "W10") (pinfunction "VSS_W10") (pintype "passive"))
      (node (ref "U1") (pin "W12") (pinfunction "VSS_W12") (pintype "passive"))
      (node (ref "U1") (pin "W14") (pinfunction "VSS_W14") (pintype "passive"))
      (node (ref "U1") (pin "W16") (pinfunction "VSS_W16") (pintype "passive"))
      (node (ref "U1") (pin "W18") (pinfunction "VSS_W18") (pintype "passive"))
      (node (ref "U1") (pin "W2") (pinfunction "VSS_W2") (pintype "passive"))
      (node (ref "U1") (pin "W20") (pinfunction "VSS_W20") (pintype "passive"))
      (node (ref "U1") (pin "W4") (pinfunction "VSS_W4") (pintype "passive"))
      (node (ref "U1") (pin "W6") (pinfunction "VSS_W6") (pintype "passive"))
      (node (ref "U1") (pin "W8") (pinfunction "VSS_W8") (pintype "passive"))
      (node (ref "U1") (pin "Y1") (pinfunction "VSS_Y1") (pintype "passive"))
      (node (ref "U1") (pin "Y11") (pinfunction "VSS_Y11") (pintype "passive"))
      (node (ref "U1") (pin "Y13") (pinfunction "VSS_Y13") (pintype "passive"))
      (node (ref "U1") (pin "Y15") (pinfunction "VSS_Y15") (pintype "passive"))
      (node (ref "U1") (pin "Y17") (pinfunction "VSS_Y17") (pintype "passive"))
      (node (ref "U1") (pin "Y19") (pinfunction "VSS_Y19") (pintype "passive"))
      (node (ref "U1") (pin "Y21") (pinfunction "VSS_Y21") (pintype "passive"))
      (node (ref "U1") (pin "Y22") (pinfunction "VSS_Y22") (pintype "passive"))
      (node (ref "U1") (pin "Y3") (pinfunction "VSS_Y3") (pintype "passive"))
      (node (ref "U1") (pin "Y5") (pinfunction "VSS_Y5") (pintype "passive"))
      (node (ref "U1") (pin "Y7") (pinfunction "VSS_Y7") (pintype "passive"))
      (node (ref "U1") (pin "Y9") (pinfunction "VSS_Y9") (pintype "passive"))
    )
  )
)
